# MM32F5277.net
KiCad netlist of a schematic drawn in Altium Designer
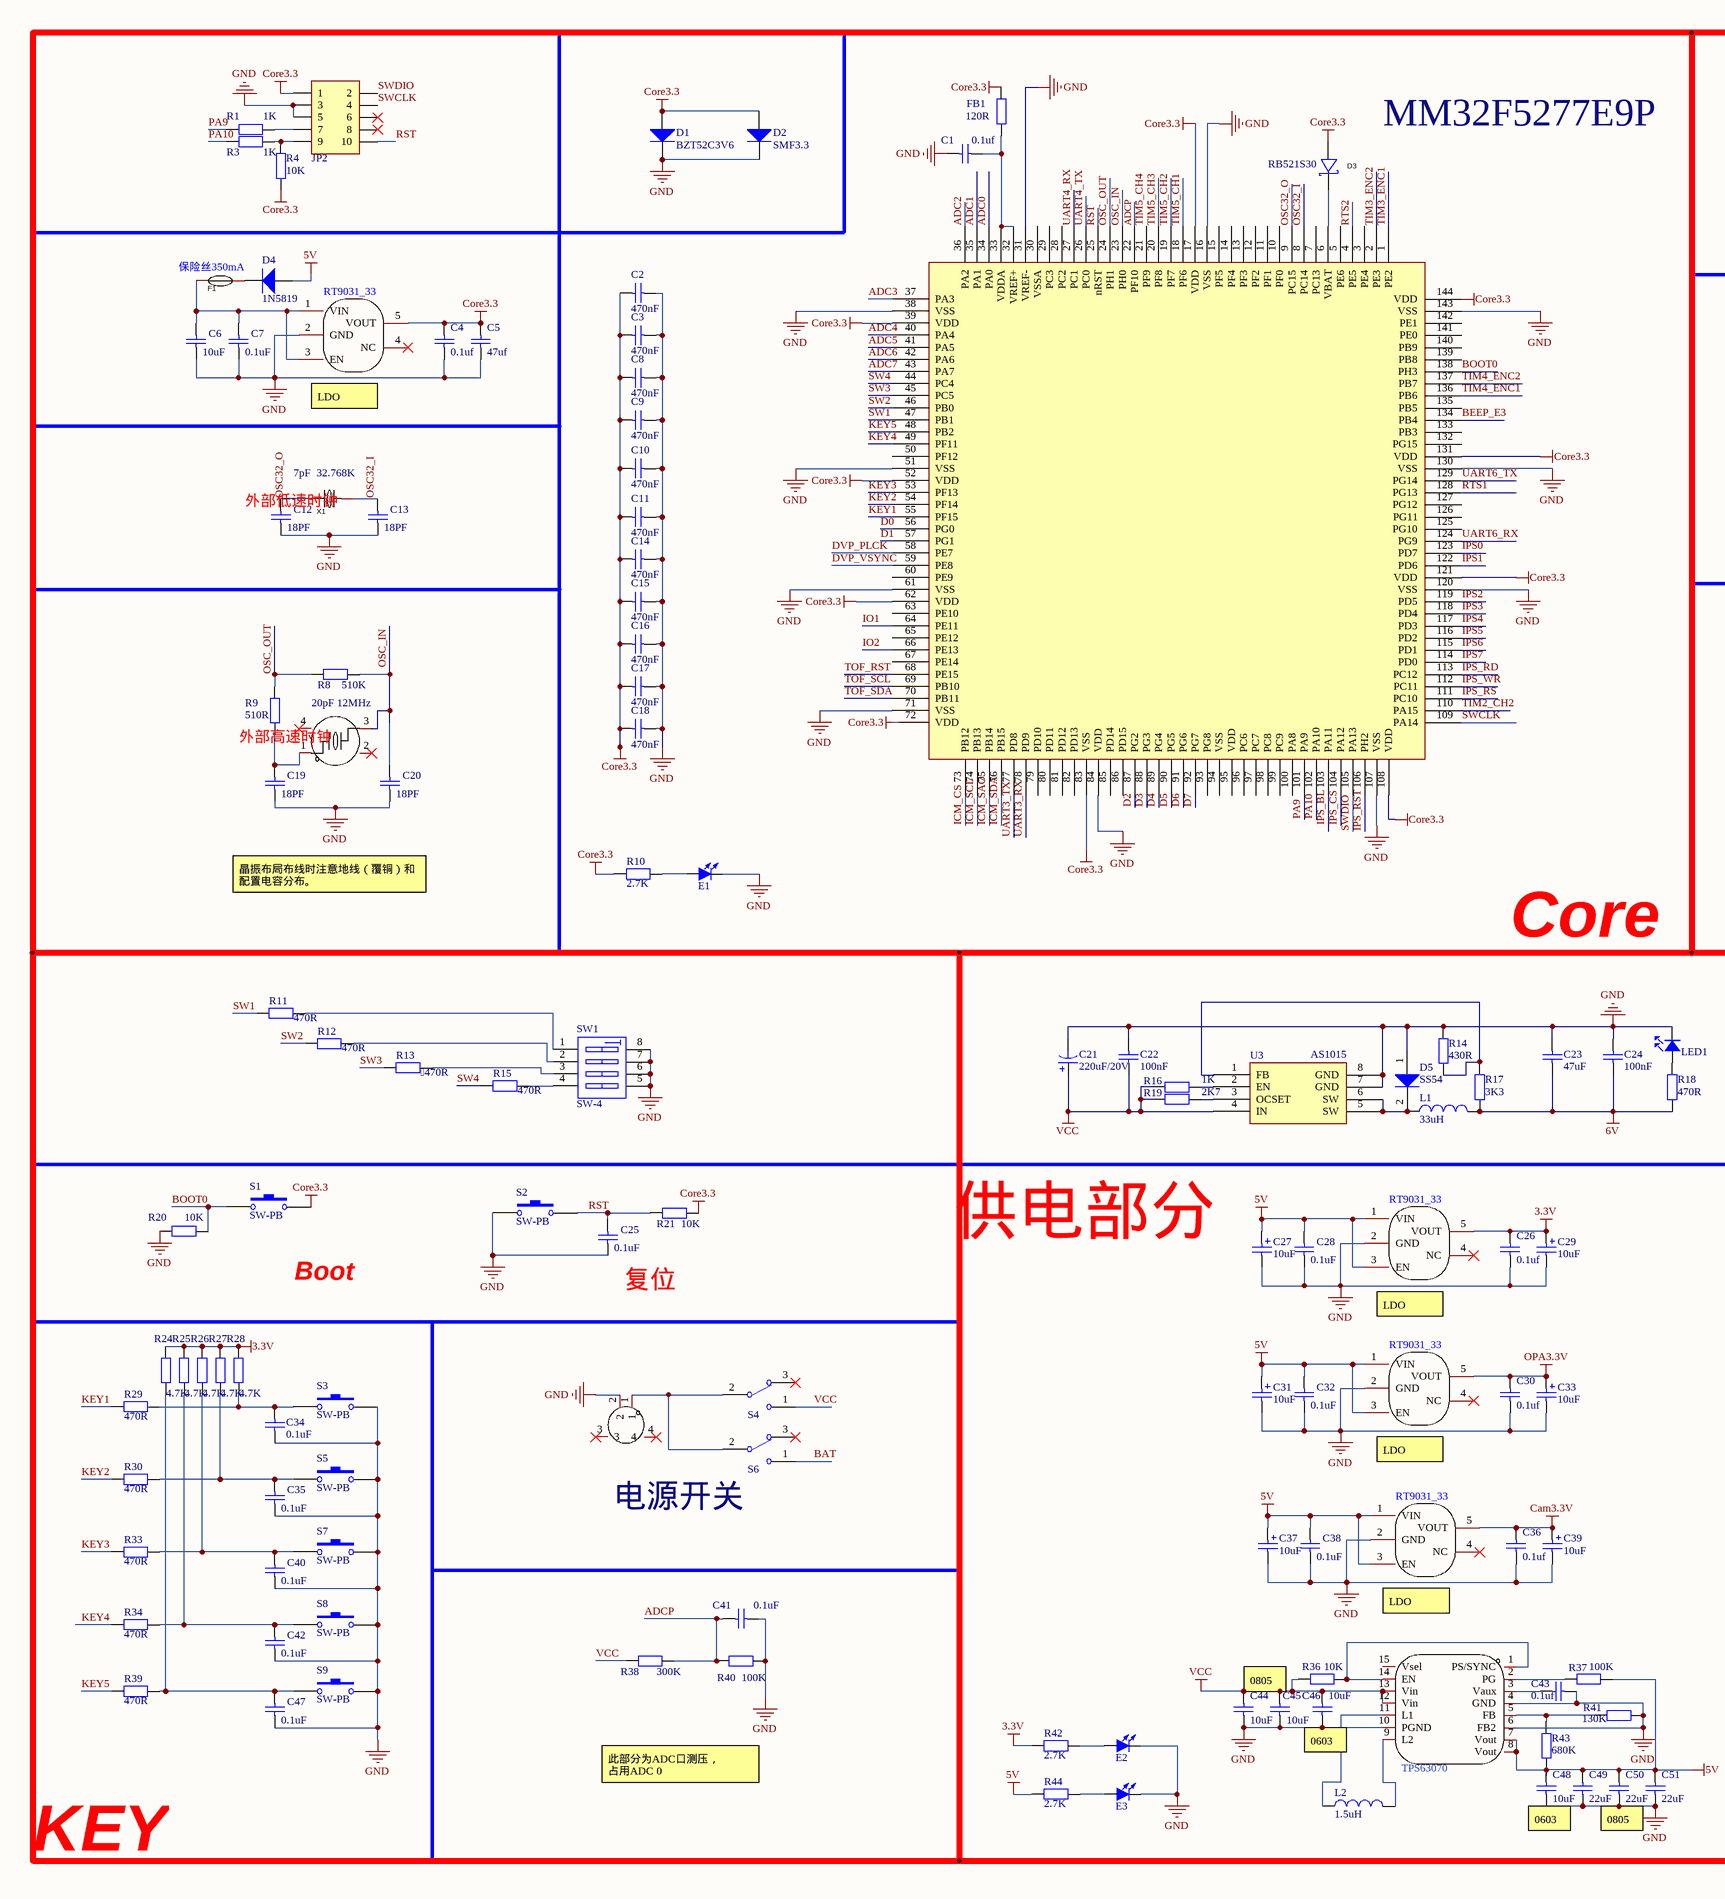
[diagram p0: MM32F5277.SchDoc, left]
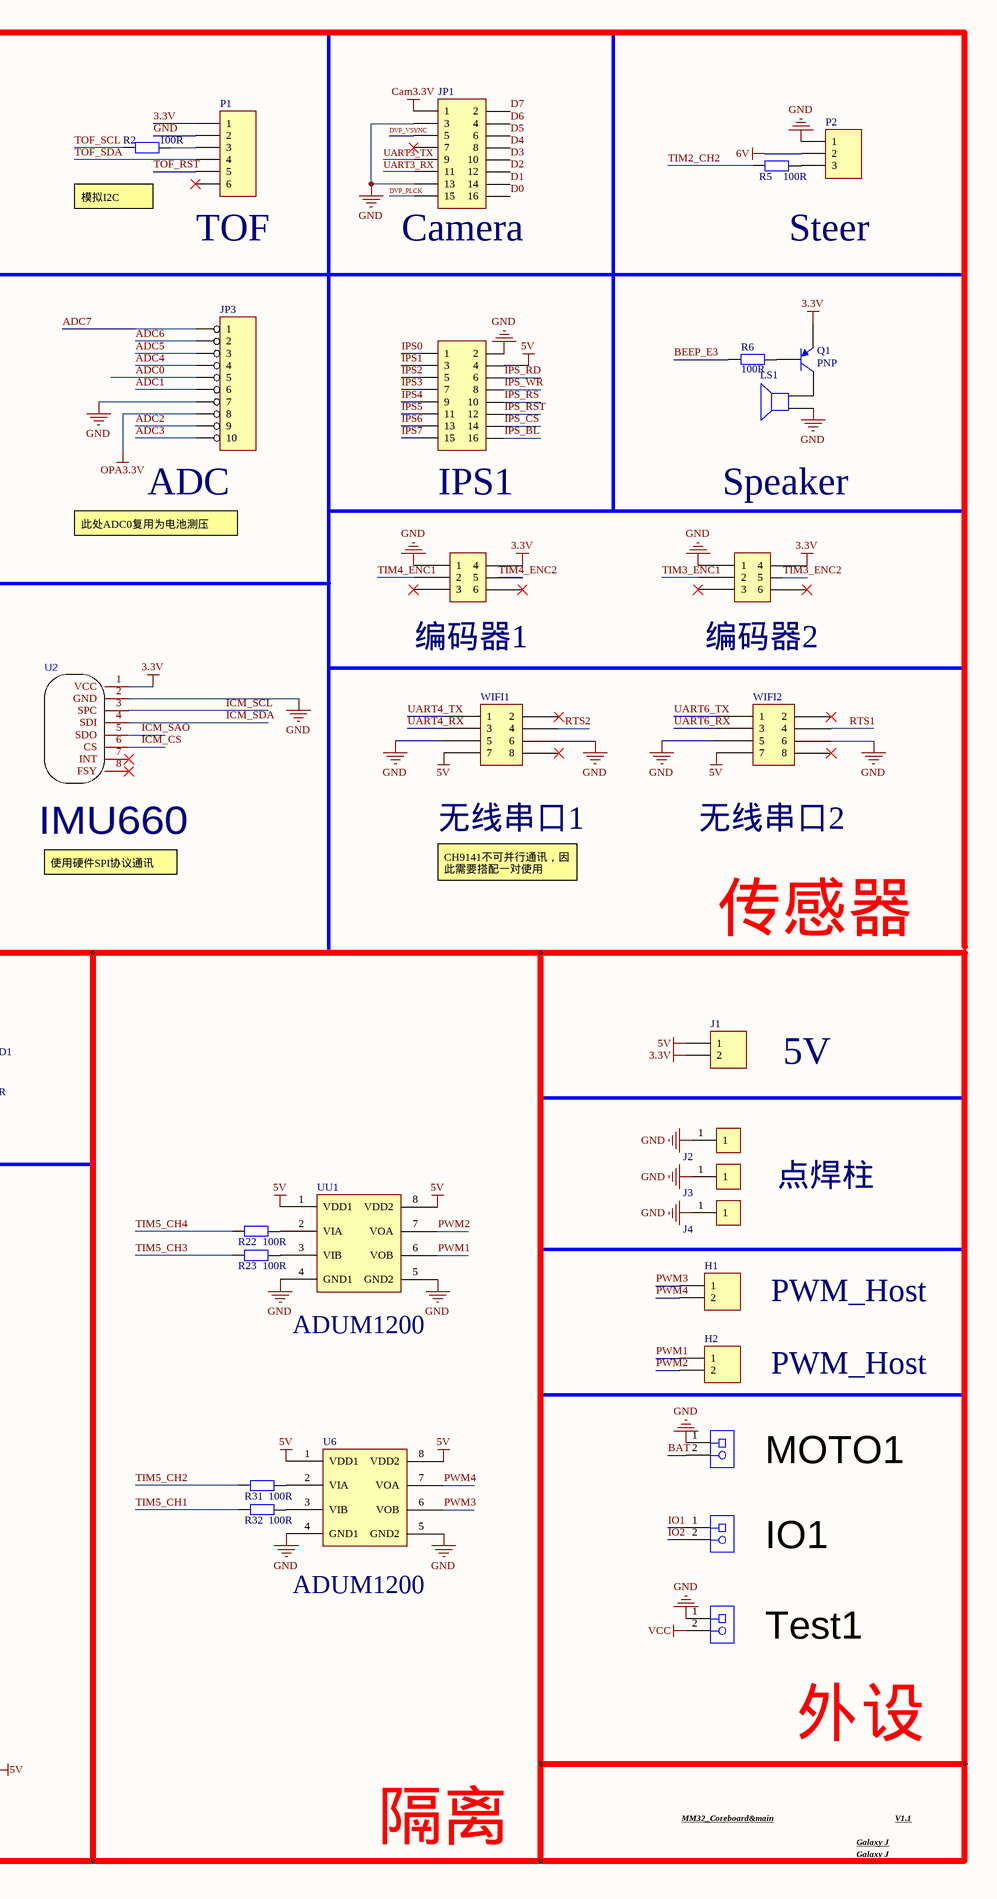
[diagram p1: MM32F5277.SchDoc, right]

(export (version "E")
  (design (tool "Eeschema 10.0.6"))
  (components
    (comp (ref "*1")
      (value "MM32F5277E9P")
      (footprint "LQFP-144_L20.0-W20.0-P0.50-LS22.0-BL")
      (libsource (lib "Mine") (part "MM32F3277G9P"))
    )
    (comp (ref "C1")
      (value "0.1uf")
      (footprint "C 0603_L")
      (fields (field (name "Comment") "Cap_4_1"))
      (libsource (lib "CAR-PCB") (part "Cap_4_1"))
    )
    (comp (ref "C2")
      (value "Cap_3")
      (footprint "C 0603_L")
      (description "Capacitor")
      (fields (field (name "ALTIUM_UNNAMED_1") "470nF"))
      (libsource (lib "CAR-PCB") (part "Cap_3"))
    )
    (comp (ref "C3")
      (value "Cap_3")
      (footprint "C 0603_L")
      (description "Capacitor")
      (fields (field (name "ALTIUM_UNNAMED_1") "470nF"))
      (libsource (lib "CAR-PCB") (part "Cap_3"))
    )
    (comp (ref "C4")
      (value "0.1uf")
      (footprint "C 0603_L")
      (fields (field (name "Comment") "Cap_4_1"))
      (libsource (lib "CAR-PCB") (part "Cap_4_1"))
    )
    (comp (ref "C5")
      (value "Cap_3")
      (footprint "C 0603_L")
      (description "Capacitor")
      (fields (field (name "ALTIUM_UNNAMED_1") "47uf"))
      (libsource (lib "CAR-PCB") (part "Cap_3"))
    )
    (comp (ref "C6")
      (value "10uF")
      (footprint "C 0603_L")
      (fields (field (name "Comment") "Cap_4_1"))
      (libsource (lib "CAR-PCB") (part "Cap_4_1"))
    )
    (comp (ref "C7")
      (value "Cap_3")
      (footprint "C 0603_L")
      (description "Capacitor")
      (fields (field (name "ALTIUM_UNNAMED_1") "0.1uF"))
      (libsource (lib "CAR-PCB") (part "Cap_3"))
    )
    (comp (ref "C8")
      (value "Cap_3")
      (footprint "C 0603_L")
      (description "Capacitor")
      (fields (field (name "ALTIUM_UNNAMED_1") "470nF"))
      (libsource (lib "CAR-PCB") (part "Cap_3"))
    )
    (comp (ref "C9")
      (value "Cap_3")
      (footprint "C 0603_L")
      (description "Capacitor")
      (fields (field (name "ALTIUM_UNNAMED_1") "470nF"))
      (libsource (lib "CAR-PCB") (part "Cap_3"))
    )
    (comp (ref "C10")
      (value "Cap_3")
      (footprint "C 0603_L")
      (description "Capacitor")
      (fields (field (name "ALTIUM_UNNAMED_1") "470nF"))
      (libsource (lib "CAR-PCB") (part "Cap_3"))
    )
    (comp (ref "C11")
      (value "Cap_3")
      (footprint "C 0603_L")
      (description "Capacitor")
      (fields (field (name "ALTIUM_UNNAMED_1") "470nF"))
      (libsource (lib "CAR-PCB") (part "Cap_3"))
    )
    (comp (ref "C12")
      (value "18PF")
      (footprint "C 0603_L")
      (fields (field (name "Comment") "Cap_4_1"))
      (libsource (lib "CAR-PCB") (part "Cap_4_1"))
    )
    (comp (ref "C13")
      (value "18PF")
      (footprint "C 0603_L")
      (fields (field (name "Comment") "Cap_4_1"))
      (libsource (lib "CAR-PCB") (part "Cap_4_1"))
    )
    (comp (ref "C14")
      (value "Cap_3")
      (footprint "C 0603_L")
      (description "Capacitor")
      (fields (field (name "ALTIUM_UNNAMED_1") "470nF"))
      (libsource (lib "CAR-PCB") (part "Cap_3"))
    )
    (comp (ref "C15")
      (value "Cap_3")
      (footprint "C 0603_L")
      (description "Capacitor")
      (fields (field (name "ALTIUM_UNNAMED_1") "470nF"))
      (libsource (lib "CAR-PCB") (part "Cap_3"))
    )
    (comp (ref "C16")
      (value "Cap_3")
      (footprint "C 0603_L")
      (description "Capacitor")
      (fields (field (name "ALTIUM_UNNAMED_1") "470nF"))
      (libsource (lib "CAR-PCB") (part "Cap_3"))
    )
    (comp (ref "C17")
      (value "Cap_3")
      (footprint "C 0603_L")
      (description "Capacitor")
      (fields (field (name "ALTIUM_UNNAMED_1") "470nF"))
      (libsource (lib "CAR-PCB") (part "Cap_3"))
    )
    (comp (ref "C18")
      (value "Cap_3")
      (footprint "C 0603_L")
      (description "Capacitor")
      (fields (field (name "ALTIUM_UNNAMED_1") "470nF"))
      (libsource (lib "CAR-PCB") (part "Cap_3"))
    )
    (comp (ref "C19")
      (value "18PF")
      (footprint "C 0603_L")
      (fields (field (name "Comment") "Cap_4_1"))
      (libsource (lib "CAR-PCB") (part "Cap_4_1"))
    )
    (comp (ref "C20")
      (value "18PF")
      (footprint "C 0603_L")
      (fields (field (name "Comment") "Cap_4_1"))
      (libsource (lib "CAR-PCB") (part "Cap_4_1"))
    )
    (comp (ref "C21")
      (value "220uF/20V")
      (footprint "CAP 5.0*10*12.5 - GD")
      (description "Polarized Capacitor (Radial)")
      (fields (field (name "PUBLISHER") "Altium Limited"))
      (libsource (lib "Miscellaneous Devices") (part "Cap Pol1"))
    )
    (comp (ref "C22")
      (value "100nF")
      (footprint "C 0603_L")
      (description "Capacitor")
      (fields (field (name "PUBLISHER") "Altium Limited"))
      (libsource (lib "Miscellaneous Devices") (part "Cap"))
    )
    (comp (ref "C23")
      (value "47uF")
      (footprint "C 1206_L")
      (description "Capacitor")
      (fields (field (name "PUBLISHER") "Altium Limited"))
      (libsource (lib "Miscellaneous Devices") (part "Cap"))
    )
    (comp (ref "C24")
      (value "100nF")
      (footprint "C 0603_L")
      (description "Capacitor")
      (fields (field (name "PUBLISHER") "Altium Limited"))
      (libsource (lib "Miscellaneous Devices") (part "Cap"))
    )
    (comp (ref "C25")
      (value "Cap_3")
      (footprint "C 0603_L")
      (description "Capacitor")
      (fields (field (name "ALTIUM_UNNAMED_1") "0.1uF"))
      (libsource (lib "CAR-PCB") (part "Cap_3"))
    )
    (comp (ref "C26")
      (value "0.1uf")
      (footprint "C 0603_L")
      (fields (field (name "Comment") "Cap_4_1"))
      (libsource (lib "CAR-PCB") (part "Cap_4_1"))
    )
    (comp (ref "C27")
      (value "10uF")
      (footprint "C3216A - duplicate - duplicate")
      (description "Polarized Capacitor (Radial)")
      (fields (field (name "Comment") "Cap Pol1") (field (name "PUBLISHER") "Altium Limited"))
      (libsource (lib "CAR-PCB") (part "Cap Pol1_1"))
    )
    (comp (ref "C28")
      (value "Cap_3")
      (footprint "C 0603_L")
      (description "Capacitor")
      (fields (field (name "ALTIUM_UNNAMED_1") "0.1uF"))
      (libsource (lib "CAR-PCB") (part "Cap_3"))
    )
    (comp (ref "C29")
      (value "10uF")
      (footprint "C3216A - duplicate - duplicate")
      (description "Polarized Capacitor (Radial)")
      (fields (field (name "Comment") "Cap Pol1") (field (name "PUBLISHER") "Altium Limited"))
      (libsource (lib "CAR-PCB") (part "Cap Pol1_1"))
    )
    (comp (ref "C30")
      (value "0.1uf")
      (footprint "C 0603_L")
      (fields (field (name "Comment") "Cap_4_1"))
      (libsource (lib "CAR-PCB") (part "Cap_4_1"))
    )
    (comp (ref "C31")
      (value "10uF")
      (footprint "C3216A - duplicate - duplicate")
      (description "Polarized Capacitor (Radial)")
      (fields (field (name "Comment") "Cap Pol1") (field (name "PUBLISHER") "Altium Limited"))
      (libsource (lib "CAR-PCB") (part "Cap Pol1_1"))
    )
    (comp (ref "C32")
      (value "Cap_3")
      (footprint "C 0603_L")
      (description "Capacitor")
      (fields (field (name "ALTIUM_UNNAMED_1") "0.1uF"))
      (libsource (lib "CAR-PCB") (part "Cap_3"))
    )
    (comp (ref "C33")
      (value "10uF")
      (footprint "C3216A - duplicate - duplicate")
      (description "Polarized Capacitor (Radial)")
      (fields (field (name "Comment") "Cap Pol1") (field (name "PUBLISHER") "Altium Limited"))
      (libsource (lib "CAR-PCB") (part "Cap Pol1_1"))
    )
    (comp (ref "C34")
      (value "Cap_3")
      (footprint "C 0603_L")
      (description "Capacitor")
      (fields (field (name "ALTIUM_UNNAMED_1") "0.1uF"))
      (libsource (lib "CAR-PCB") (part "Cap_3"))
    )
    (comp (ref "C35")
      (value "Cap_3")
      (footprint "C 0603_L")
      (description "Capacitor")
      (fields (field (name "ALTIUM_UNNAMED_1") "0.1uF"))
      (libsource (lib "CAR-PCB") (part "Cap_3"))
    )
    (comp (ref "C36")
      (value "0.1uf")
      (footprint "C 0603_L")
      (fields (field (name "Comment") "Cap_4_1"))
      (libsource (lib "CAR-PCB") (part "Cap_4_1"))
    )
    (comp (ref "C37")
      (value "10uF")
      (footprint "C3216A - duplicate - duplicate")
      (description "Polarized Capacitor (Radial)")
      (fields (field (name "Comment") "Cap Pol1") (field (name "PUBLISHER") "Altium Limited"))
      (libsource (lib "CAR-PCB") (part "Cap Pol1_1"))
    )
    (comp (ref "C38")
      (value "Cap_3")
      (footprint "C 0603_L")
      (description "Capacitor")
      (fields (field (name "ALTIUM_UNNAMED_1") "0.1uF"))
      (libsource (lib "CAR-PCB") (part "Cap_3"))
    )
    (comp (ref "C39")
      (value "10uF")
      (footprint "C3216A - duplicate - duplicate")
      (description "Polarized Capacitor (Radial)")
      (fields (field (name "Comment") "Cap Pol1") (field (name "PUBLISHER") "Altium Limited"))
      (libsource (lib "CAR-PCB") (part "Cap Pol1_1"))
    )
    (comp (ref "C40")
      (value "Cap_3")
      (footprint "C 0603_L")
      (description "Capacitor")
      (fields (field (name "ALTIUM_UNNAMED_1") "0.1uF"))
      (libsource (lib "CAR-PCB") (part "Cap_3"))
    )
    (comp (ref "C41")
      (value "Cap_3")
      (footprint "C 0603_L")
      (description "Capacitor")
      (fields (field (name "ALTIUM_UNNAMED_1") "0.1uF"))
      (libsource (lib "CAR-PCB") (part "Cap_3"))
    )
    (comp (ref "C42")
      (value "Cap_3")
      (footprint "C 0603_L")
      (description "Capacitor")
      (fields (field (name "ALTIUM_UNNAMED_1") "0.1uF"))
      (libsource (lib "CAR-PCB") (part "Cap_3"))
    )
    (comp (ref "C43")
      (value "0.1uf")
      (footprint "C 0603_L")
      (fields (field (name "Comment") "Cap_4_1"))
      (libsource (lib "CAR-PCB") (part "Cap_4_1"))
    )
    (comp (ref "C44")
      (value "10uF")
      (footprint "C 0805_L")
      (fields (field (name "Comment") "Cap_4_1"))
      (libsource (lib "CAR-PCB") (part "Cap_4_1"))
    )
    (comp (ref "C45")
      (value "10uF")
      (footprint "C 0805_L")
      (fields (field (name "Comment") "Cap_4_1"))
      (libsource (lib "CAR-PCB") (part "Cap_4_1"))
    )
    (comp (ref "C46")
      (value "10uF")
      (footprint "C 0603_L")
      (fields (field (name "Comment") "Cap_4_1"))
      (libsource (lib "CAR-PCB") (part "Cap_4_1"))
    )
    (comp (ref "C47")
      (value "Cap_3")
      (footprint "C 0603_L")
      (description "Capacitor")
      (fields (field (name "ALTIUM_UNNAMED_1") "0.1uF"))
      (libsource (lib "CAR-PCB") (part "Cap_3"))
    )
    (comp (ref "C48")
      (value "10uF")
      (footprint "C 0603_L")
      (fields (field (name "Comment") "Cap_4_1"))
      (libsource (lib "CAR-PCB") (part "Cap_4_1"))
    )
    (comp (ref "C49")
      (value "22uF")
      (footprint "C 0805_L")
      (fields (field (name "Comment") "Cap_4_1"))
      (libsource (lib "CAR-PCB") (part "Cap_4_1"))
    )
    (comp (ref "C50")
      (value "22uF")
      (footprint "C 0805_L")
      (fields (field (name "Comment") "Cap_4_1"))
      (libsource (lib "CAR-PCB") (part "Cap_4_1"))
    )
    (comp (ref "C51")
      (value "22uF")
      (footprint "C 0805_L")
      (fields (field (name "Comment") "Cap_4_1"))
      (libsource (lib "CAR-PCB") (part "Cap_4_1"))
    )
    (comp (ref "CN1")
      (value "XT30PW-M")
      (footprint "XT30PW-M")
      (fields (field (name "MANUFACTURER") "AMASS(艾迈斯)"))
      (libsource (lib "XT30PW-M1_XT30PW-M") (part "XT30PW-M"))
    )
    (comp (ref "D1")
      (value "BZT52C3V6")
      (footprint "SOD-123")
      (description "SMT Glass Diode, PSpice Model")
      (fields (field (name "PARTNUMBER") "BZT52C3V6") (field (name "PUBLISHER") "Altium Limited"))
      (libsource (lib "altium-import") (part "root_3_Diode 1N4148_"))
    )
    (comp (ref "D2")
      (value "SMF3.3")
      (footprint "SOD-123")
      (description "SMT Glass Diode, PSpice Model")
      (fields (field (name "PARTNUMBER") "SMF3.3") (field (name "PUBLISHER") "Altium Limited"))
      (libsource (lib "altium-import") (part "root_3_Diode 1N4148_"))
    )
    (comp (ref "D3")
      (value "RB521S30")
      (footprint "SOD-523_L1.2-W0.8-LS1.6-RD")
      (fields (field (name "MANUFACTURER") "onsemi(安森美)"))
      (libsource (lib "Schlib1") (part "RB521S30"))
    )
    (comp (ref "D4")
      (value "1N5819")
      (footprint "SOD-123")
      (description "SMT Glass Diode, PSpice Model")
      (fields (field (name "PARTNUMBER") "1N5819") (field (name "PUBLISHER") "Altium Limited"))
      (libsource (lib "altium-import") (part "root_2_Diode 1N4148_"))
    )
    (comp (ref "D5")
      (value "SS54")
      (footprint "SMA")
      (description "3 Amp Medium Power Silicon Rectifier Diode")
      (fields (field (name "PUBLISHER") "Altium Limited"))
      (libsource (lib "Miscellaneous Devices") (part "Diode 1N5408"))
    )
    (comp (ref "E1")
      (value "红色")
      (footprint "LED 0603")
      (description "贴片LED")
      (fields (field (name "版权归属") "黎明电子style"))
      (libsource (lib "CAR-PCB") (part "LED-SMD"))
    )
    (comp (ref "E2")
      (value "红色")
      (footprint "LED 0603")
      (description "贴片LED")
      (fields (field (name "版权归属") "黎明电子style"))
      (libsource (lib "CAR-PCB") (part "LED-SMD"))
    )
    (comp (ref "E3")
      (value "红色")
      (footprint "LED 0603")
      (description "贴片LED")
      (fields (field (name "版权归属") "黎明电子style"))
      (libsource (lib "CAR-PCB") (part "LED-SMD"))
    )
    (comp (ref "F1")
      (value "0603L050SLYR")
      (footprint "FU 0805")
      (fields (field (name "MANUFACTURER") "Littelfuse(美国力特)"))
      (libsource (lib "6V500mA") (part "0603L050SLYR"))
    )
    (comp (ref "FB1")
      (value "120R")
      (footprint "R 0603_L")
      (description "FB")
      (fields (field (name "PUBLISHER") "Altium Limited"))
      (libsource (lib "") (part "Res2_1"))
    )
    (comp (ref "H1")
      (value "PWM_Host")
      (footprint "HX2.54-2")
      (description "Header, 2-Pin")
      (fields (field (name "PUBLISHER") "Altium Limited"))
      (libsource (lib "Miscellaneous Connectors") (part "Header 2"))
    )
    (comp (ref "H2")
      (value "PWM_Host")
      (footprint "HX2.54-2")
      (description "Header, 2-Pin")
      (fields (field (name "PUBLISHER") "Altium Limited"))
      (libsource (lib "Miscellaneous Connectors") (part "Header 2"))
    )
    (comp (ref "IO1")
      (value "KF301-2P")
      (footprint "HDR1X2")
      (description "IO")
      (fields
        (field (name "PARTNUMBER") "691 101 710 002")
        (field (name "MANUFACTURER") "Wurth Elektronik eiSos")
        (field (name "SYMBOLCREATOR") "a0412235")
        (field (name "PUBLISHER") "Texas Instruments")
      )
      (libsource (lib "LQ-PCB(1)") (part "691 101 710 001"))
    )
    (comp (ref "IPS1")
      (value "Header 8X2")
      (footprint "HDR-8X2")
      (description "8*2P接插件")
      (fields (field (name "版权归属") "黎明电子style"))
      (libsource (lib "LQTC(逐飞)") (part "Header 8X2"))
    )
    (comp (ref "J1")
      (value "5V")
      (footprint "HDR2.54-1X2")
      (description "Header, 2-Pin")
      (fields (field (name "PUBLISHER") "Altium Limited"))
      (libsource (lib "Miscellaneous Connectors") (part "Header 2"))
    )
    (comp (ref "J2") (value "Column") (footprint "Column") (libsource (lib "Schlib1") (part "Component_1")))
    (comp (ref "J3") (value "Column") (footprint "Column") (libsource (lib "Schlib1") (part "Component_1")))
    (comp (ref "J4") (value "点焊柱") (footprint "Column") (libsource (lib "Schlib1") (part "Component_1")))
    (comp (ref "JP1") (value "Camera") (footprint "Cam_HDR2X8") (libsource (lib "CAR-PCB") (part "Camera")))
    (comp (ref "JP2")
      (value "Header 5X2")
      (footprint "HDR2.54-LI-2x5P")
      (description "5*2P接插件")
      (libsource (lib "18 - 接插件-脚距2.54mm (100mil) ") (part "Header 5X2"))
    )
    (comp (ref "JP3")
      (value "ADC")
      (footprint "HDR1X10")
      (libsource (lib "Miscellaneous Devices") (part "HEADER 10"))
    )
    (comp (ref "L1")
      (value "33uH")
      (footprint "L-SMD-0630")
      (description "Inductor")
      (fields (field (name "PUBLISHER") "Altium Limited"))
      (libsource (lib "Miscellaneous Devices") (part "Inductor"))
    )
    (comp (ref "L2")
      (value "1.5uH")
      (footprint "L-SMD-0630")
      (description "Inductor")
      (fields (field (name "PUBLISHER") "Altium Limited"))
      (libsource (lib "Miscellaneous Devices") (part "Inductor"))
    )
    (comp (ref "LED1") (value "LED-SM") (footprint "LED 0603") (libsource (lib "LZLIB2010") (part "LED-SM")))
    (comp (ref "LS1")
      (value "Speaker")
      (footprint "BEEP 9x5.5mm")
      (description "Loudspeaker")
      (fields (field (name "PUBLISHER") "Altium Limited"))
      (libsource (lib "2014主板3.0") (part "Speaker"))
    )
    (comp (ref "mini*1")
      (value "编码器2")
      (footprint "DC-2.54-L-Z-6P")
      (libsource (lib "LQ-PCB(1)") (part "Component_1"))
    )
    (comp (ref "mini1")
      (value "编码器1")
      (footprint "DC-2.54-L-Z-6P")
      (libsource (lib "LQ-PCB(1)") (part "Component_1"))
    )
    (comp (ref "MOTO1")
      (value "KF301-2P")
      (footprint "XT30UPB-F")
      (fields
        (field (name "PARTNUMBER") "691 101 710 002")
        (field (name "MANUFACTURER") "Wurth Elektronik eiSos")
        (field (name "SYMBOLCREATOR") "a0412235")
        (field (name "PUBLISHER") "Texas Instruments")
      )
      (libsource (lib "LQ-PCB(1)") (part "691 101 710 001"))
    )
    (comp (ref "P1")
      (value "TOF")
      (footprint "HDR1X6-M")
      (description "Header, 6-Pin")
      (fields (field (name "PUBLISHER") "Altium Limited"))
      (libsource (lib "Miscellaneous Connectors") (part "Header 6"))
    )
    (comp (ref "P2")
      (value "Steer")
      (footprint "HDR2.54-LI-3P")
      (description "Header, 3-Pin")
      (fields (field (name "PUBLISHER") "Altium Limited"))
      (libsource (lib "LQ-PCB(1)") (part "Header 3"))
    )
    (comp (ref "Q1")
      (value "PNP")
      (footprint "SOT23-3L")
      (description "PNP Bipolar Transistor")
      (fields (field (name "PUBLISHER") "Altium Limited"))
      (libsource (lib "20170112") (part "PNP"))
    )
    (comp (ref "R1")
      (value "1K")
      (footprint "R 0603_L")
      (description "Resistor")
      (fields (field (name "Comment") "Res2") (field (name "PUBLISHER") "Altium Limited"))
      (libsource (lib "LQ-PCB(1)") (part "Res2"))
    )
    (comp (ref "R2")
      (value "100R")
      (footprint "R 0603_L")
      (description "Resistor")
      (fields (field (name "Comment") "Res2") (field (name "PUBLISHER") "Altium Limited"))
      (libsource (lib "LQ-PCB(1)") (part "Res2"))
    )
    (comp (ref "R3")
      (value "1K")
      (footprint "R 0603_L")
      (description "Resistor")
      (fields (field (name "Comment") "Res2") (field (name "PUBLISHER") "Altium Limited"))
      (libsource (lib "LQ-PCB(1)") (part "Res2"))
    )
    (comp (ref "R4")
      (value "10K")
      (footprint "R 0603_L")
      (description "Resistor")
      (fields (field (name "Comment") "Res2") (field (name "PUBLISHER") "Altium Limited"))
      (libsource (lib "") (part "Res2_1"))
    )
    (comp (ref "R5")
      (value "100R")
      (footprint "R 0603_L")
      (description "Resistor")
      (fields (field (name "Comment") "Res2") (field (name "PUBLISHER") "Altium Limited"))
      (libsource (lib "LQ-PCB(1)") (part "Res2"))
    )
    (comp (ref "R6")
      (value "100R")
      (footprint "R 0603_L")
      (fields (field (name "Comment") "Res2_3"))
      (libsource (lib "") (part "Res2_3_1"))
    )
    (comp (ref "R8")
      (value "510K")
      (footprint "R 0603_L")
      (description "Resistor")
      (fields (field (name "Comment") "Res2") (field (name "PUBLISHER") "Altium Limited"))
      (libsource (lib "LQ-PCB(1)") (part "Res2"))
    )
    (comp (ref "R9")
      (value "510R")
      (footprint "R 0603_L")
      (description "Resistor")
      (fields (field (name "Comment") "Res2") (field (name "PUBLISHER") "Altium Limited"))
      (libsource (lib "") (part "Res2_1"))
    )
    (comp (ref "R10")
      (value "2.7K")
      (footprint "R 0603_L")
      (fields (field (name "Comment") "Res2_3"))
      (libsource (lib "") (part "Res2_3_1"))
    )
    (comp (ref "R11")
      (value "470R")
      (footprint "R 0603_L")
      (description "Resistor")
      (fields (field (name "Comment") "Res2") (field (name "PUBLISHER") "Altium Limited"))
      (libsource (lib "") (part "Res2_2_1"))
    )
    (comp (ref "R12")
      (value "470R")
      (footprint "R 0603_L")
      (description "Resistor")
      (fields (field (name "Comment") "Res2") (field (name "PUBLISHER") "Altium Limited"))
      (libsource (lib "") (part "Res2_2_1"))
    )
    (comp (ref "R13")
      (value "470R")
      (footprint "R 0603_L")
      (description "Resistor")
      (fields (field (name "Comment") "Res2") (field (name "PUBLISHER") "Altium Limited"))
      (libsource (lib "") (part "Res2_2_1"))
    )
    (comp (ref "R14")
      (value "430R")
      (footprint "R 0603_L")
      (description "Resistor")
      (fields (field (name "PUBLISHER") "Altium Limited"))
      (libsource (lib "") (part "R6_1"))
    )
    (comp (ref "R15")
      (value "470R")
      (footprint "R 0603_L")
      (description "Resistor")
      (fields (field (name "Comment") "Res2") (field (name "PUBLISHER") "Altium Limited"))
      (libsource (lib "") (part "Res2_2_1"))
    )
    (comp (ref "R16")
      (value "1K")
      (footprint "R 0603_L")
      (description "Resistor")
      (fields (field (name "PUBLISHER") "Altium Limited"))
      (libsource (lib "YUNFANG") (part "R6"))
    )
    (comp (ref "R17")
      (value "3K3")
      (footprint "R 0603_L")
      (description "Resistor")
      (fields (field (name "PUBLISHER") "Altium Limited"))
      (libsource (lib "") (part "R6_1"))
    )
    (comp (ref "R18")
      (value "470R")
      (footprint "R 0603_L")
      (description "Resistor")
      (fields (field (name "PUBLISHER") "Altium Limited"))
      (libsource (lib "") (part "R6_2"))
    )
    (comp (ref "R19")
      (value "2K7")
      (footprint "R 0603_L")
      (description "Resistor")
      (fields (field (name "PUBLISHER") "Altium Limited"))
      (libsource (lib "YUNFANG") (part "R6"))
    )
    (comp (ref "R20")
      (value "10K")
      (footprint "R 0603_L")
      (description "Resistor")
      (fields (field (name "Comment") "Res2") (field (name "PUBLISHER") "Altium Limited"))
      (libsource (lib "LQ-PCB(1)") (part "Res2"))
    )
    (comp (ref "R21")
      (value "10K")
      (footprint "R 0603_L")
      (description "Resistor")
      (fields (field (name "Comment") "Res2") (field (name "PUBLISHER") "Altium Limited"))
      (libsource (lib "LQ-PCB(1)") (part "Res2"))
    )
    (comp (ref "R22")
      (value "100R")
      (footprint "R 0603_L")
      (description "Resistor")
      (fields (field (name "Comment") "Res2") (field (name "PUBLISHER") "Altium Limited"))
      (libsource (lib "LQ-PCB(1)") (part "Res2"))
    )
    (comp (ref "R23")
      (value "100R")
      (footprint "R 0603_L")
      (description "Resistor")
      (fields (field (name "Comment") "Res2") (field (name "PUBLISHER") "Altium Limited"))
      (libsource (lib "LQ-PCB(1)") (part "Res2"))
    )
    (comp (ref "R24")
      (value "4.7K")
      (footprint "R 0603_L")
      (description "Resistor")
      (fields (field (name "Comment") "Res2") (field (name "PUBLISHER") "Altium Limited"))
      (libsource (lib "CAR-PCB") (part "Res2_2"))
    )
    (comp (ref "R25")
      (value "4.7K")
      (footprint "R 0603_L")
      (description "Resistor")
      (fields (field (name "Comment") "Res2") (field (name "PUBLISHER") "Altium Limited"))
      (libsource (lib "CAR-PCB") (part "Res2_2"))
    )
    (comp (ref "R26")
      (value "4.7K")
      (footprint "R 0603_L")
      (description "Resistor")
      (fields (field (name "Comment") "Res2") (field (name "PUBLISHER") "Altium Limited"))
      (libsource (lib "CAR-PCB") (part "Res2_2"))
    )
    (comp (ref "R27")
      (value "4.7K")
      (footprint "R 0603_L")
      (description "Resistor")
      (fields (field (name "Comment") "Res2") (field (name "PUBLISHER") "Altium Limited"))
      (libsource (lib "CAR-PCB") (part "Res2_2"))
    )
    (comp (ref "R28")
      (value "4.7K")
      (footprint "R 0603_L")
      (description "Resistor")
      (fields (field (name "Comment") "Res2") (field (name "PUBLISHER") "Altium Limited"))
      (libsource (lib "CAR-PCB") (part "Res2_2"))
    )
    (comp (ref "R29")
      (value "470R")
      (footprint "R 0603_L")
      (description "Resistor")
      (fields (field (name "Comment") "Res2") (field (name "PUBLISHER") "Altium Limited"))
      (libsource (lib "") (part "Res2_2_1"))
    )
    (comp (ref "R30")
      (value "470R")
      (footprint "R 0603_L")
      (description "Resistor")
      (fields (field (name "Comment") "Res2") (field (name "PUBLISHER") "Altium Limited"))
      (libsource (lib "") (part "Res2_2_1"))
    )
    (comp (ref "R31")
      (value "100R")
      (footprint "R 0603_L")
      (description "Resistor")
      (fields (field (name "Comment") "Res2") (field (name "PUBLISHER") "Altium Limited"))
      (libsource (lib "LQ-PCB(1)") (part "Res2"))
    )
    (comp (ref "R32")
      (value "100R")
      (footprint "R 0603_L")
      (description "Resistor")
      (fields (field (name "Comment") "Res2") (field (name "PUBLISHER") "Altium Limited"))
      (libsource (lib "LQ-PCB(1)") (part "Res2"))
    )
    (comp (ref "R33")
      (value "470R")
      (footprint "R 0603_L")
      (description "Resistor")
      (fields (field (name "Comment") "Res2") (field (name "PUBLISHER") "Altium Limited"))
      (libsource (lib "") (part "Res2_2_1"))
    )
    (comp (ref "R34")
      (value "470R")
      (footprint "R 0603_L")
      (description "Resistor")
      (fields (field (name "Comment") "Res2") (field (name "PUBLISHER") "Altium Limited"))
      (libsource (lib "") (part "Res2_2_1"))
    )
    (comp (ref "R36")
      (value "10K")
      (footprint "R 0603_L")
      (fields (field (name "Comment") "Res2_3"))
      (libsource (lib "") (part "Res2_3_2"))
    )
    (comp (ref "R37")
      (value "100K")
      (footprint "R 0603_L")
      (fields (field (name "Comment") "Res2_3"))
      (libsource (lib "") (part "Res2_3_2"))
    )
    (comp (ref "R38")
      (value "300K")
      (footprint "R 0603_L")
      (description "Resistor")
      (fields (field (name "Comment") "Res2") (field (name "PUBLISHER") "Altium Limited"))
      (libsource (lib "LQ-PCB(1)") (part "Res2"))
    )
    (comp (ref "R39")
      (value "470R")
      (footprint "R 0603_L")
      (description "Resistor")
      (fields (field (name "Comment") "Res2") (field (name "PUBLISHER") "Altium Limited"))
      (libsource (lib "") (part "Res2_2_1"))
    )
    (comp (ref "R40")
      (value "100K")
      (footprint "R 0603_L")
      (description "Resistor")
      (fields (field (name "Comment") "Res2") (field (name "PUBLISHER") "Altium Limited"))
      (libsource (lib "LQ-PCB(1)") (part "Res2"))
    )
    (comp (ref "R41")
      (value "130K")
      (footprint "R 0603_L")
      (fields (field (name "Comment") "Res2_3"))
      (libsource (lib "") (part "Res2_3_1"))
    )
    (comp (ref "R42")
      (value "2.7K")
      (footprint "R 0603_L")
      (fields (field (name "Comment") "Res2_3"))
      (libsource (lib "") (part "Res2_3_1"))
    )
    (comp (ref "R43")
      (value "680K")
      (footprint "R 0603_L")
      (fields (field (name "Comment") "Res2_3"))
      (libsource (lib "CAR-PCB") (part "Res2_3"))
    )
    (comp (ref "R44")
      (value "2.7K")
      (footprint "R 0603_L")
      (fields (field (name "Comment") "Res2_3"))
      (libsource (lib "") (part "Res2_3_1"))
    )
    (comp (ref "S1")
      (value "SW-PB")
      (footprint "PTS810-3*4-CurvePin")
      (description "微动开关")
      (fields (field (name "PUBLISHER") "Altium Limited"))
      (libsource (lib "0.7 - 常用按键-开关") (part "SW-PB"))
    )
    (comp (ref "S2")
      (value "SW-PB")
      (footprint "PTS810-3*4-CurvePin")
      (description "微动开关")
      (fields (field (name "PUBLISHER") "Altium Limited"))
      (libsource (lib "0.7 - 常用按键-开关") (part "SW-PB"))
    )
    (comp (ref "S3")
      (value "SW-PB")
      (footprint "PTS810-3*4-CurvePin")
      (description "微动开关")
      (fields (field (name "PUBLISHER") "Altium Limited"))
      (libsource (lib "0.7 - 常用按键-开关") (part "SW-PB"))
    )
    (comp (ref "S4")
      (value "SW-SPDT")
      (footprint "SS12D10")
      (description "单刀双掷开关 3脚船型、钮子、拨动开关 SPDT Subminiature Toggle Switch")
      (fields (field (name "PUBLISHER") "Altium Limited"))
      (libsource (lib "钮子开关原理") (part "SW-SPDT"))
    )
    (comp (ref "S5")
      (value "SW-PB")
      (footprint "PTS810-3*4-CurvePin")
      (description "微动开关")
      (fields (field (name "PUBLISHER") "Altium Limited"))
      (libsource (lib "0.7 - 常用按键-开关") (part "SW-PB"))
    )
    (comp (ref "S6")
      (value "SW-SPDT")
      (footprint "SS12D10")
      (description "单刀双掷开关 3脚船型、钮子、拨动开关 SPDT Subminiature Toggle Switch")
      (fields (field (name "PUBLISHER") "Altium Limited"))
      (libsource (lib "钮子开关原理") (part "SW-SPDT"))
    )
    (comp (ref "S7")
      (value "SW-PB")
      (footprint "PTS810-3*4-CurvePin")
      (description "微动开关")
      (fields (field (name "PUBLISHER") "Altium Limited"))
      (libsource (lib "0.7 - 常用按键-开关") (part "SW-PB"))
    )
    (comp (ref "S8")
      (value "SW-PB")
      (footprint "PTS810-3*4-CurvePin")
      (description "微动开关")
      (fields (field (name "PUBLISHER") "Altium Limited"))
      (libsource (lib "0.7 - 常用按键-开关") (part "SW-PB"))
    )
    (comp (ref "S9")
      (value "SW-PB")
      (footprint "PTS810-3*4-CurvePin")
      (description "微动开关")
      (fields (field (name "PUBLISHER") "Altium Limited"))
      (libsource (lib "0.7 - 常用按键-开关") (part "SW-PB"))
    )
    (comp (ref "SW1") (value "SW-4") (footprint "SOP-KEY4") (libsource (lib "LQ-PCB(1)") (part "SW-4")))
    (comp (ref "Test1")
      (value "KF301-2P")
      (footprint "HDR2.54-1X2 - duplicate1")
      (fields
        (field (name "PARTNUMBER") "691 101 710 002")
        (field (name "MANUFACTURER") "Wurth Elektronik eiSos")
        (field (name "SYMBOLCREATOR") "a0412235")
        (field (name "PUBLISHER") "Texas Instruments")
      )
      (libsource (lib "LQ-PCB(1)") (part "691 101 710 001"))
    )
    (comp (ref "U1")
      (value "RT9013-33GB")
      (footprint "MM32F5277主板封装库:SOT-23-5")
      (fields (field (name "MANUFACTURER") "RICHTEK(台湾立锜)"))
      (libsource (lib "RT9013-33GB") (part "RT9013-33GB"))
    )
    (comp (ref "U2") (value "IMU660") (footprint "HDR1X6-M") (libsource (lib "icm20602") (part "ICM20602")))
    (comp (ref "U3") (value "AS1015") (footprint "SOP8_L") (libsource (lib "*") (part "AS1015")))
    (comp (ref "U4")
      (value "RT9013-33GB")
      (footprint "MM32F5277主板封装库:SOT-23-5")
      (fields (field (name "MANUFACTURER") "RICHTEK(台湾立锜)"))
      (libsource (lib "RT9013-33GB") (part "RT9013-33GB"))
    )
    (comp (ref "U5")
      (value "RT9013-33GB")
      (footprint "MM32F5277主板封装库:SOT-23-5")
      (fields (field (name "MANUFACTURER") "RICHTEK(台湾立锜)"))
      (libsource (lib "RT9013-33GB") (part "RT9013-33GB"))
    )
    (comp (ref "U6") (value "ADUM1200") (footprint "SOP8_L") (libsource (lib "20170112") (part "ADUM1201")))
    (comp (ref "U7")
      (value "RT9013-33GB")
      (footprint "MM32F5277主板封装库:SOT-23-5")
      (fields (field (name "MANUFACTURER") "RICHTEK(台湾立锜)"))
      (libsource (lib "RT9013-33GB") (part "RT9013-33GB"))
    )
    (comp (ref "U8")
      (value "TPS63070RNMR")
      (footprint "VQFN-HR-15_L3.0-W2.5-P0.50-BL_TPS63070RNMR")
      (fields (field (name "MANUFACTURER") "TI(德州仪器)"))
      (libsource (lib "TPS63070RNMR") (part "TPS63070RNMR"))
    )
    (comp (ref "UU1") (value "ADUM1200") (footprint "SOP8_L") (libsource (lib "20170112") (part "ADUM1201")))
    (comp (ref "WIFI1")
      (value "无线串口1")
      (footprint "HDR2.54-LI-2x4P")
      (libsource (lib "插件") (part "HEADER2X4"))
    )
    (comp (ref "WIFI2")
      (value "无线串口2")
      (footprint "HDR2.54-LI-2x4P")
      (libsource (lib "插件") (part "HEADER2X4"))
    )
    (comp (ref "X1")
      (value "7pF  32.768K")
      (footprint "OSC 3215-2P")
      (fields
        (field (name "MANUFACTURER") "Seiko(精工)")
        (field (name "MANUFACTURER PART") "SC-32S32.768kHz20PPM12.5pF")
      )
      (libsource (lib "altium-import") (part "root_2_SC-32S32.768kHz20PPM12.5pF_"))
    )
    (comp (ref "X2")
      (value "20pF 12MHz")
      (footprint "X3225-4")
      (description "12MHZ")
      (fields (field (name "MANUFACTURER") "YXC扬兴科技") (field (name "MANUFACTURER PART") "X32258MSB4SI"))
      (libsource (lib "X32258MSB4SI1_X32258MSB4SI") (part "X32258MSB4SI"))
    )
  )
  (nets
    (net (code "1") (name "/ADC0") (class "Default")
      (node (ref "*1") (pin "34") (pinfunction "PA0_34") (pintype "passive"))
      (node (ref "JP3") (pin "5") (pinfunction "5_5") (pintype "passive"))
    )
    (net (code "2") (name "/ADC1") (class "Default")
      (node (ref "*1") (pin "35") (pinfunction "PA1_35") (pintype "passive"))
      (node (ref "JP3") (pin "6") (pinfunction "6_6") (pintype "passive"))
    )
    (net (code "3") (name "/ADC2") (class "Default")
      (node (ref "*1") (pin "36") (pinfunction "PA2_36") (pintype "passive"))
      (node (ref "JP3") (pin "9") (pinfunction "9_9") (pintype "passive"))
    )
    (net (code "4") (name "/ADC3") (class "Default")
      (node (ref "*1") (pin "37") (pinfunction "PA3_37") (pintype "passive"))
      (node (ref "JP3") (pin "10") (pinfunction "10_10") (pintype "passive"))
    )
    (net (code "5") (name "/ADC4") (class "Default")
      (node (ref "*1") (pin "40") (pinfunction "PA4_40") (pintype "passive"))
      (node (ref "JP3") (pin "4") (pinfunction "4_4") (pintype "passive"))
    )
    (net (code "6") (name "/ADC5") (class "Default")
      (node (ref "*1") (pin "41") (pinfunction "PA5_41") (pintype "passive"))
      (node (ref "JP3") (pin "3") (pinfunction "3_3") (pintype "passive"))
    )
    (net (code "7") (name "/ADC6") (class "Default")
      (node (ref "*1") (pin "42") (pinfunction "PA6_42") (pintype "passive"))
      (node (ref "JP3") (pin "2") (pinfunction "2_2") (pintype "passive"))
    )
    (net (code "8") (name "/ADC7") (class "Default")
      (node (ref "*1") (pin "43") (pinfunction "PA7_43") (pintype "passive"))
      (node (ref "JP3") (pin "1") (pinfunction "1_1") (pintype "passive"))
    )
    (net (code "9") (name "/ADCP") (class "Default")
      (node (ref "*1") (pin "22") (pinfunction "PF10_22") (pintype "passive"))
      (node (ref "C41") (pin "2") (pinfunction "2_2") (pintype "passive"))
      (node (ref "R38") (pin "2") (pinfunction "2_2") (pintype "passive"))
      (node (ref "R40") (pin "1") (pinfunction "1_1") (pintype "passive"))
    )
    (net (code "10") (name "/BAT") (class "Default")
      (node (ref "MOTO1") (pin "2") (pinfunction "2_2") (pintype "passive"))
      (node (ref "S6") (pin "1") (pintype "passive"))
    )
    (net (code "11") (name "/BEEP_E3") (class "Default")
      (node (ref "*1") (pin "134") (pinfunction "PB4_134") (pintype "passive"))
      (node (ref "R6") (pin "1") (pinfunction "1_1") (pintype "passive"))
    )
    (net (code "12") (name "/BOOT0") (class "Default")
      (node (ref "*1") (pin "138") (pinfunction "PH3_138") (pintype "passive"))
      (node (ref "R20") (pin "2") (pinfunction "2_2") (pintype "passive"))
      (node (ref "S1") (pin "1") (pinfunction "1_1") (pintype "passive"))
    )
    (net (code "13") (name "/D0") (class "Default")
      (node (ref "*1") (pin "56") (pinfunction "PG0_56") (pintype "passive"))
      (node (ref "JP1") (pin "16") (pinfunction "16_16") (pintype "passive"))
    )
    (net (code "14") (name "/D1") (class "Default")
      (node (ref "*1") (pin "57") (pinfunction "PG1_57") (pintype "passive"))
      (node (ref "JP1") (pin "14") (pinfunction "14_14") (pintype "passive"))
    )
    (net (code "15") (name "/D2") (class "Default")
      (node (ref "*1") (pin "87") (pinfunction "PG2_87") (pintype "passive"))
      (node (ref "JP1") (pin "12") (pinfunction "12_12") (pintype "passive"))
    )
    (net (code "16") (name "/D3") (class "Default")
      (node (ref "*1") (pin "88") (pinfunction "PG3_88") (pintype "passive"))
      (node (ref "JP1") (pin "10") (pinfunction "10_10") (pintype "passive"))
    )
    (net (code "17") (name "/D4") (class "Default")
      (node (ref "*1") (pin "89") (pinfunction "PG4_89") (pintype "passive"))
      (node (ref "JP1") (pin "8") (pinfunction "8_8") (pintype "passive"))
    )
    (net (code "18") (name "/D5") (class "Default")
      (node (ref "*1") (pin "90") (pinfunction "PG5_90") (pintype "passive"))
      (node (ref "JP1") (pin "6") (pinfunction "6_6") (pintype "passive"))
    )
    (net (code "19") (name "/D6") (class "Default")
      (node (ref "*1") (pin "91") (pinfunction "PG6_91") (pintype "passive"))
      (node (ref "JP1") (pin "4") (pinfunction "4_4") (pintype "passive"))
    )
    (net (code "20") (name "/D7") (class "Default")
      (node (ref "*1") (pin "92") (pinfunction "PG7_92") (pintype "passive"))
      (node (ref "JP1") (pin "2") (pinfunction "2_2") (pintype "passive"))
    )
    (net (code "21") (name "/DVP_PLCK") (class "Default")
      (node (ref "*1") (pin "58") (pinfunction "PE7_58") (pintype "passive"))
      (node (ref "JP1") (pin "15") (pinfunction "15_15") (pintype "passive"))
    )
    (net (code "22") (name "/DVP_VSYNC") (class "Default")
      (node (ref "*1") (pin "59") (pinfunction "PE8_59") (pintype "passive"))
      (node (ref "JP1") (pin "5") (pinfunction "5_5") (pintype "passive"))
    )
    (net (code "23") (name "/ICM_CS") (class "Default")
      (node (ref "*1") (pin "73") (pinfunction "PB12_73") (pintype "passive"))
      (node (ref "U2") (pin "6") (pinfunction "CS_6") (pintype "passive"))
    )
    (net (code "24") (name "/ICM_SAO") (class "Default")
      (node (ref "*1") (pin "75") (pinfunction "PB14_75") (pintype "passive"))
      (node (ref "U2") (pin "5") (pinfunction "SDO_5") (pintype "passive"))
    )
    (net (code "25") (name "/ICM_SCL") (class "Default")
      (node (ref "*1") (pin "74") (pinfunction "PB13_74") (pintype "passive"))
      (node (ref "U2") (pin "3") (pinfunction "SPC_3") (pintype "passive"))
    )
    (net (code "26") (name "/ICM_SDA") (class "Default")
      (node (ref "*1") (pin "76") (pinfunction "PB15_76") (pintype "passive"))
      (node (ref "U2") (pin "4") (pinfunction "SDI_4") (pintype "passive"))
    )
    (net (code "27") (name "/IO1") (class "Default")
      (node (ref "*1") (pin "64") (pinfunction "PE11_64") (pintype "passive"))
      (node (ref "IO1") (pin "1") (pinfunction "1_1") (pintype "passive"))
    )
    (net (code "28") (name "/IO2") (class "Default")
      (node (ref "*1") (pin "66") (pinfunction "PE13_66") (pintype "passive"))
      (node (ref "IO1") (pin "2") (pinfunction "2_2") (pintype "passive"))
    )
    (net (code "29") (name "/IPS0") (class "Default")
      (node (ref "*1") (pin "123") (pinfunction "PD7_123") (pintype "passive"))
      (node (ref "IPS1") (pin "1") (pinfunction "1_1") (pintype "passive"))
    )
    (net (code "30") (name "/IPS1") (class "Default")
      (node (ref "*1") (pin "122") (pinfunction "PD6_122") (pintype "passive"))
      (node (ref "IPS1") (pin "3") (pinfunction "3_3") (pintype "passive"))
    )
    (net (code "31") (name "/IPS2") (class "Default")
      (node (ref "*1") (pin "119") (pinfunction "PD5_119") (pintype "passive"))
      (node (ref "IPS1") (pin "5") (pinfunction "5_5") (pintype "passive"))
    )
    (net (code "32") (name "/IPS3") (class "Default")
      (node (ref "*1") (pin "118") (pinfunction "PD4_118") (pintype "passive"))
      (node (ref "IPS1") (pin "7") (pinfunction "7_7") (pintype "passive"))
    )
    (net (code "33") (name "/IPS4") (class "Default")
      (node (ref "*1") (pin "117") (pinfunction "PD3_117") (pintype "passive"))
      (node (ref "IPS1") (pin "9") (pinfunction "9_9") (pintype "passive"))
    )
    (net (code "34") (name "/IPS5") (class "Default")
      (node (ref "*1") (pin "116") (pinfunction "PD2_116") (pintype "passive"))
      (node (ref "IPS1") (pin "11") (pinfunction "11_11") (pintype "passive"))
    )
    (net (code "35") (name "/IPS6") (class "Default")
      (node (ref "*1") (pin "115") (pinfunction "PD1_115") (pintype "passive"))
      (node (ref "IPS1") (pin "13") (pinfunction "13_13") (pintype "passive"))
    )
    (net (code "36") (name "/IPS7") (class "Default")
      (node (ref "*1") (pin "114") (pinfunction "PD0_114") (pintype "passive"))
      (node (ref "IPS1") (pin "15") (pinfunction "15_15") (pintype "passive"))
    )
    (net (code "37") (name "/IPS_BL") (class "Default")
      (node (ref "*1") (pin "103") (pinfunction "PA11_103") (pintype "passive"))
      (node (ref "IPS1") (pin "16") (pinfunction "16_16") (pintype "passive"))
    )
    (net (code "38") (name "/IPS_CS") (class "Default")
      (node (ref "*1") (pin "104") (pinfunction "PA12_104") (pintype "passive"))
      (node (ref "IPS1") (pin "14") (pinfunction "14_14") (pintype "passive"))
    )
    (net (code "39") (name "/IPS_RD") (class "Default")
      (node (ref "*1") (pin "113") (pinfunction "PC12_113") (pintype "passive"))
      (node (ref "IPS1") (pin "6") (pinfunction "6_6") (pintype "passive"))
    )
    (net (code "40") (name "/IPS_RS") (class "Default")
      (node (ref "*1") (pin "111") (pinfunction "PC10_111") (pintype "passive"))
      (node (ref "IPS1") (pin "10") (pinfunction "10_10") (pintype "passive"))
    )
    (net (code "41") (name "/IPS_RST") (class "Default")
      (node (ref "*1") (pin "106") (pinfunction "PH2_106") (pintype "passive"))
      (node (ref "IPS1") (pin "12") (pinfunction "12_12") (pintype "passive"))
    )
    (net (code "42") (name "/IPS_WR") (class "Default")
      (node (ref "*1") (pin "112") (pinfunction "PC11_112") (pintype "passive"))
      (node (ref "IPS1") (pin "8") (pinfunction "8_8") (pintype "passive"))
    )
    (net (code "43") (name "/KEY1") (class "Default")
      (node (ref "*1") (pin "55") (pinfunction "PF15_55") (pintype "passive"))
      (node (ref "R29") (pin "1") (pinfunction "1_1") (pintype "passive"))
    )
    (net (code "44") (name "/KEY2") (class "Default")
      (node (ref "*1") (pin "54") (pinfunction "PF14_54") (pintype "passive"))
      (node (ref "R30") (pin "1") (pinfunction "1_1") (pintype "passive"))
    )
    (net (code "45") (name "/KEY3") (class "Default")
      (node (ref "*1") (pin "53") (pinfunction "PF13_53") (pintype "passive"))
      (node (ref "R33") (pin "1") (pinfunction "1_1") (pintype "passive"))
    )
    (net (code "46") (name "/KEY4") (class "Default")
      (node (ref "*1") (pin "49") (pinfunction "PF11_49") (pintype "passive"))
      (node (ref "R34") (pin "1") (pinfunction "1_1") (pintype "passive"))
    )
    (net (code "47") (name "/KEY5") (class "Default")
      (node (ref "*1") (pin "48") (pinfunction "PB2_48") (pintype "passive"))
      (node (ref "R39") (pin "1") (pinfunction "1_1") (pintype "passive"))
    )
    (net (code "48") (name "/OSC32_I") (class "Default")
      (node (ref "*1") (pin "8") (pinfunction "PC14_8") (pintype "passive"))
      (node (ref "C13") (pin "2") (pinfunction "2_2") (pintype "passive"))
      (node (ref "X1") (pin "1") (pinfunction "1_1") (pintype "passive"))
    )
    (net (code "49") (name "/OSC32_O") (class "Default")
      (node (ref "*1") (pin "9") (pinfunction "PC15_9") (pintype "passive"))
      (node (ref "C12") (pin "2") (pinfunction "2_2") (pintype "passive"))
      (node (ref "X1") (pin "2") (pinfunction "2_2") (pintype "passive"))
    )
    (net (code "50") (name "/OSC_IN") (class "Default")
      (node (ref "*1") (pin "23") (pinfunction "PH0_23") (pintype "passive"))
      (node (ref "C20") (pin "2") (pinfunction "2_2") (pintype "passive"))
      (node (ref "R8") (pin "2") (pinfunction "2_2") (pintype "passive"))
      (node (ref "X2") (pin "3") (pinfunction "3_3") (pintype "passive"))
    )
    (net (code "51") (name "/OSC_OUT") (class "Default")
      (node (ref "*1") (pin "24") (pinfunction "PH1_24") (pintype "passive"))
      (node (ref "R8") (pin "1") (pinfunction "1_1") (pintype "passive"))
      (node (ref "R9") (pin "2") (pinfunction "2_2") (pintype "passive"))
    )
    (net (code "52") (name "/PA9") (class "Default")
      (node (ref "*1") (pin "101") (pinfunction "PA9_101") (pintype "passive"))
      (node (ref "R1") (pin "1") (pinfunction "1_1") (pintype "passive"))
    )
    (net (code "53") (name "/PA10") (class "Default")
      (node (ref "*1") (pin "102") (pinfunction "PA10_102") (pintype "passive"))
      (node (ref "R3") (pin "1") (pinfunction "1_1") (pintype "passive"))
    )
    (net (code "54") (name "/PWM1") (class "Default")
      (node (ref "H2") (pin "1") (pinfunction "1_1") (pintype "passive"))
      (node (ref "UU1") (pin "6") (pinfunction "VOB_6") (pintype "passive"))
    )
    (net (code "55") (name "/PWM2") (class "Default")
      (node (ref "H2") (pin "2") (pinfunction "2_2") (pintype "passive"))
      (node (ref "UU1") (pin "7") (pinfunction "VOA_7") (pintype "passive"))
    )
    (net (code "56") (name "/PWM3") (class "Default")
      (node (ref "H1") (pin "1") (pinfunction "1_1") (pintype "passive"))
      (node (ref "U6") (pin "6") (pinfunction "VOB_6") (pintype "passive"))
    )
    (net (code "57") (name "/PWM4") (class "Default")
      (node (ref "H1") (pin "2") (pinfunction "2_2") (pintype "passive"))
      (node (ref "U6") (pin "7") (pinfunction "VOA_7") (pintype "passive"))
    )
    (net (code "58") (name "/RST") (class "Default")
      (node (ref "*1") (pin "25") (pinfunction "nRST_25") (pintype "passive"))
      (node (ref "C25") (pin "2") (pinfunction "2_2") (pintype "passive"))
      (node (ref "JP2") (pin "10") (pinfunction "10_10") (pintype "passive"))
      (node (ref "R21") (pin "1") (pinfunction "1_1") (pintype "passive"))
      (node (ref "S2") (pin "2") (pinfunction "2_2") (pintype "passive"))
    )
    (net (code "59") (name "/RTS1") (class "Default")
      (node (ref "*1") (pin "128") (pinfunction "PG13_128") (pintype "passive"))
      (node (ref "WIFI2") (pin "4") (pinfunction "4_4") (pintype "power_in"))
    )
    (net (code "60") (name "/RTS2") (class "Default")
      (node (ref "*1") (pin "4") (pinfunction "PE5_4") (pintype "passive"))
      (node (ref "WIFI1") (pin "4") (pinfunction "4_4") (pintype "power_in"))
    )
    (net (code "61") (name "/SW1") (class "Default")
      (node (ref "*1") (pin "47") (pinfunction "PB1_47") (pintype "passive"))
      (node (ref "R11") (pin "1") (pinfunction "1_1") (pintype "passive"))
    )
    (net (code "62") (name "/SW2") (class "Default")
      (node (ref "*1") (pin "46") (pinfunction "PB0_46") (pintype "passive"))
      (node (ref "R12") (pin "1") (pinfunction "1_1") (pintype "passive"))
    )
    (net (code "63") (name "/SW3") (class "Default")
      (node (ref "*1") (pin "45") (pinfunction "PC5_45") (pintype "passive"))
      (node (ref "R13") (pin "1") (pinfunction "1_1") (pintype "passive"))
    )
    (net (code "64") (name "/SW4") (class "Default")
      (node (ref "*1") (pin "44") (pinfunction "PC4_44") (pintype "passive"))
      (node (ref "R15") (pin "1") (pinfunction "1_1") (pintype "passive"))
    )
    (net (code "65") (name "/SWCLK") (class "Default")
      (node (ref "*1") (pin "109") (pinfunction "PA14_109") (pintype "passive"))
      (node (ref "JP2") (pin "4") (pinfunction "4_4") (pintype "passive"))
    )
    (net (code "66") (name "/SWDIO") (class "Default")
      (node (ref "*1") (pin "105") (pinfunction "PA13_105") (pintype "passive"))
      (node (ref "JP2") (pin "2") (pinfunction "2_2") (pintype "passive"))
    )
    (net (code "67") (name "/TIM2_CH2") (class "Default")
      (node (ref "*1") (pin "110") (pinfunction "PA15_110") (pintype "passive"))
      (node (ref "R5") (pin "1") (pinfunction "1_1") (pintype "passive"))
    )
    (net (code "68") (name "/TIM3_ENC1") (class "Default")
      (node (ref "*1") (pin "1") (pinfunction "PE2_1") (pintype "passive"))
      (node (ref "mini*1") (pin "2") (pinfunction "2_2") (pintype "passive"))
    )
    (net (code "69") (name "/TIM3_ENC2") (class "Default")
      (node (ref "*1") (pin "2") (pinfunction "PE3_2") (pintype "passive"))
      (node (ref "mini*1") (pin "5") (pinfunction "5_5") (pintype "passive"))
    )
    (net (code "70") (name "/TIM4_ENC1") (class "Default")
      (node (ref "*1") (pin "136") (pinfunction "PB6_136") (pintype "passive"))
      (node (ref "mini1") (pin "2") (pinfunction "2_2") (pintype "passive"))
    )
    (net (code "71") (name "/TIM4_ENC2") (class "Default")
      (node (ref "*1") (pin "137") (pinfunction "PB7_137") (pintype "passive"))
      (node (ref "mini1") (pin "5") (pinfunction "5_5") (pintype "passive"))
    )
    (net (code "72") (name "/TIM5_CH1") (class "Default")
      (node (ref "*1") (pin "18") (pinfunction "PF6_18") (pintype "passive"))
      (node (ref "R32") (pin "1") (pinfunction "1_1") (pintype "passive"))
    )
    (net (code "73") (name "/TIM5_CH2") (class "Default")
      (node (ref "*1") (pin "19") (pinfunction "PF7_19") (pintype "passive"))
      (node (ref "R31") (pin "1") (pinfunction "1_1") (pintype "passive"))
    )
    (net (code "74") (name "/TIM5_CH3") (class "Default")
      (node (ref "*1") (pin "20") (pinfunction "PF8_20") (pintype "passive"))
      (node (ref "R23") (pin "1") (pinfunction "1_1") (pintype "passive"))
    )
    (net (code "75") (name "/TIM5_CH4") (class "Default")
      (node (ref "*1") (pin "21") (pinfunction "PF9_21") (pintype "passive"))
      (node (ref "R22") (pin "1") (pinfunction "1_1") (pintype "passive"))
    )
    (net (code "76") (name "/TOF_RST") (class "Default")
      (node (ref "*1") (pin "68") (pinfunction "PE15_68") (pintype "passive"))
      (node (ref "P1") (pin "5") (pinfunction "5_5") (pintype "passive"))
    )
    (net (code "77") (name "/TOF_SCL") (class "Default")
      (node (ref "*1") (pin "69") (pinfunction "PB10_69") (pintype "passive"))
      (node (ref "R2") (pin "1") (pinfunction "1_1") (pintype "passive"))
    )
    (net (code "78") (name "/TOF_SDA") (class "Default")
      (node (ref "*1") (pin "70") (pinfunction "PB11_70") (pintype "passive"))
      (node (ref "P1") (pin "4") (pinfunction "4_4") (pintype "passive"))
    )
    (net (code "79") (name "/UART3_RX") (class "Default")
      (node (ref "*1") (pin "78") (pinfunction "PD9_78") (pintype "passive"))
      (node (ref "JP1") (pin "11") (pinfunction "11_11") (pintype "passive"))
    )
    (net (code "80") (name "/UART3_TX") (class "Default")
      (node (ref "*1") (pin "77") (pinfunction "PD8_77") (pintype "passive"))
      (node (ref "JP1") (pin "9") (pinfunction "9_9") (pintype "passive"))
    )
    (net (code "81") (name "/UART4_RX") (class "Default")
      (node (ref "*1") (pin "27") (pinfunction "PC1_27") (pintype "passive"))
      (node (ref "WIFI1") (pin "3") (pinfunction "3_3") (pintype "power_in"))
    )
    (net (code "82") (name "/UART4_TX") (class "Default")
      (node (ref "*1") (pin "26") (pinfunction "PC0_26") (pintype "passive"))
      (node (ref "WIFI1") (pin "1") (pinfunction "1_1") (pintype "passive"))
    )
    (net (code "83") (name "/UART6_RX") (class "Default")
      (node (ref "*1") (pin "124") (pinfunction "PG9_124") (pintype "passive"))
      (node (ref "WIFI2") (pin "3") (pinfunction "3_3") (pintype "power_in"))
    )
    (net (code "84") (name "/UART6_TX") (class "Default")
      (node (ref "*1") (pin "129") (pinfunction "PG14_129") (pintype "passive"))
      (node (ref "WIFI2") (pin "1") (pinfunction "1_1") (pintype "passive"))
    )
    (net (code "85") (name "3.3V") (class "Default")
      (node (ref "C26") (pin "2") (pinfunction "2_2") (pintype "passive"))
      (node (ref "C29") (pin "1") (pinfunction "1_1") (pintype "passive"))
      (node (ref "J1") (pin "2") (pinfunction "2_2") (pintype "passive"))
      (node (ref "P1") (pin "1") (pinfunction "1_1") (pintype "passive"))
      (node (ref "Q1") (pin "3") (pinfunction "E_3") (pintype "passive"))
      (node (ref "R24") (pin "1") (pinfunction "1_1") (pintype "passive"))
      (node (ref "R25") (pin "1") (pinfunction "1_1") (pintype "passive"))
      (node (ref "R26") (pin "1") (pinfunction "1_1") (pintype "passive"))
      (node (ref "R27") (pin "1") (pinfunction "1_1") (pintype "passive"))
      (node (ref "R28") (pin "1") (pinfunction "1_1") (pintype "passive"))
      (node (ref "R42") (pin "1") (pinfunction "1_1") (pintype "passive"))
      (node (ref "U2") (pin "1") (pinfunction "VCC_1") (pintype "passive"))
      (node (ref "U4") (pin "5") (pinfunction "VOUT_5") (pintype "passive"))
      (node (ref "mini*1") (pin "4") (pinfunction "4_4") (pintype "passive"))
      (node (ref "mini1") (pin "4") (pinfunction "4_4") (pintype "passive"))
    )
    (net (code "86") (name "5V") (class "Default")
      (node (ref "C27") (pin "1") (pinfunction "1_1") (pintype "passive"))
      (node (ref "C28") (pin "2") (pinfunction "2_2") (pintype "passive"))
      (node (ref "C31") (pin "1") (pinfunction "1_1") (pintype "passive"))
      (node (ref "C32") (pin "2") (pinfunction "2_2") (pintype "passive"))
      (node (ref "C37") (pin "1") (pinfunction "1_1") (pintype "passive"))
      (node (ref "C38") (pin "2") (pinfunction "2_2") (pintype "passive"))
      (node (ref "C48") (pin "2") (pinfunction "2_2") (pintype "passive"))
      (node (ref "C49") (pin "1") (pinfunction "1_1") (pintype "passive"))
      (node (ref "C50") (pin "2") (pinfunction "2_2") (pintype "passive"))
      (node (ref "C51") (pin "2") (pinfunction "2_2") (pintype "passive"))
      (node (ref "D4") (pin "A") (pinfunction "A_A") (pintype "passive"))
      (node (ref "IPS1") (pin "4") (pinfunction "4_4") (pintype "passive"))
      (node (ref "J1") (pin "1") (pinfunction "1_1") (pintype "passive"))
      (node (ref "R37") (pin "1") (pinfunction "1_1") (pintype "passive"))
      (node (ref "R43") (pin "1") (pinfunction "1_1") (pintype "passive"))
      (node (ref "R44") (pin "1") (pinfunction "1_1") (pintype "passive"))
      (node (ref "U4") (pin "1") (pinfunction "VIN_1") (pintype "passive"))
      (node (ref "U4") (pin "3") (pinfunction "EN_3") (pintype "passive"))
      (node (ref "U5") (pin "1") (pinfunction "VIN_1") (pintype "passive"))
      (node (ref "U5") (pin "3") (pinfunction "EN_3") (pintype "passive"))
      (node (ref "U6") (pin "1") (pinfunction "VDD1_1") (pintype "passive"))
      (node (ref "U6") (pin "8") (pinfunction "VDD2_8") (pintype "passive"))
      (node (ref "U7") (pin "1") (pinfunction "VIN_1") (pintype "passive"))
      (node (ref "U7") (pin "3") (pinfunction "EN_3") (pintype "passive"))
      (node (ref "U8") (pin "7") (pinfunction "Vout_7") (pintype "passive"))
      (node (ref "U8") (pin "8") (pinfunction "Vout_8") (pintype "passive"))
      (node (ref "UU1") (pin "1") (pinfunction "VDD1_1") (pintype "passive"))
      (node (ref "UU1") (pin "8") (pinfunction "VDD2_8") (pintype "passive"))
      (node (ref "WIFI1") (pin "7") (pinfunction "7_7") (pintype "power_in"))
      (node (ref "WIFI2") (pin "7") (pinfunction "7_7") (pintype "power_in"))
    )
    (net (code "87") (name "6V") (class "Default")
      (node (ref "C23") (pin "1") (pinfunction "1_1") (pintype "passive"))
      (node (ref "C24") (pin "1") (pinfunction "1_1") (pintype "passive"))
      (node (ref "L1") (pin "2") (pinfunction "2_2") (pintype "passive"))
      (node (ref "P2") (pin "2") (pinfunction "2_2") (pintype "passive"))
      (node (ref "R17") (pin "1") (pinfunction "1_1") (pintype "passive"))
      (node (ref "R18") (pin "2") (pinfunction "2_2") (pintype "passive"))
    )
    (net (code "88") (name "Cam3.3V") (class "Default")
      (node (ref "C36") (pin "2") (pinfunction "2_2") (pintype "passive"))
      (node (ref "C39") (pin "1") (pinfunction "1_1") (pintype "passive"))
      (node (ref "JP1") (pin "1") (pinfunction "1_1") (pintype "passive"))
      (node (ref "U7") (pin "5") (pinfunction "VOUT_5") (pintype "passive"))
    )
    (net (code "89") (name "Core3.3") (class "Default")
      (node (ref "*1") (pin "108") (pinfunction "VDD_108") (pintype "passive"))
      (node (ref "*1") (pin "121") (pinfunction "VDD_121") (pintype "passive"))
      (node (ref "*1") (pin "131") (pinfunction "VDD_131") (pintype "passive"))
      (node (ref "*1") (pin "144") (pinfunction "VDD_144") (pintype "passive"))
      (node (ref "*1") (pin "17") (pinfunction "VDD_17") (pintype "passive"))
      (node (ref "*1") (pin "39") (pinfunction "VDD_39") (pintype "passive"))
      (node (ref "*1") (pin "52") (pinfunction "VDD_52") (pintype "passive"))
      (node (ref "*1") (pin "62") (pinfunction "VDD_62") (pintype "passive"))
      (node (ref "*1") (pin "72") (pinfunction "VDD_72") (pintype "passive"))
      (node (ref "*1") (pin "83") (pinfunction "VSS_83") (pintype "passive"))
      (node (ref "C10") (pin "2") (pinfunction "2_2") (pintype "passive"))
      (node (ref "C11") (pin "2") (pinfunction "2_2") (pintype "passive"))
      (node (ref "C14") (pin "2") (pinfunction "2_2") (pintype "passive"))
      (node (ref "C15") (pin "2") (pinfunction "2_2") (pintype "passive"))
      (node (ref "C16") (pin "2") (pinfunction "2_2") (pintype "passive"))
      (node (ref "C17") (pin "2") (pinfunction "2_2") (pintype "passive"))
      (node (ref "C18") (pin "2") (pinfunction "2_2") (pintype "passive"))
      (node (ref "C2") (pin "2") (pinfunction "2_2") (pintype "passive"))
      (node (ref "C3") (pin "2") (pinfunction "2_2") (pintype "passive"))
      (node (ref "C4") (pin "2") (pinfunction "2_2") (pintype "passive"))
      (node (ref "C5") (pin "2") (pinfunction "2_2") (pintype "passive"))
      (node (ref "C8") (pin "2") (pinfunction "2_2") (pintype "passive"))
      (node (ref "C9") (pin "2") (pinfunction "2_2") (pintype "passive"))
      (node (ref "D1") (pin "A") (pinfunction "A_A") (pintype "passive"))
      (node (ref "D2") (pin "A") (pinfunction "A_A") (pintype "passive"))
      (node (ref "D3") (pin "2") (pinfunction "A_2") (pintype "passive"))
      (node (ref "FB1") (pin "2") (pinfunction "2_2") (pintype "passive"))
      (node (ref "JP2") (pin "1") (pinfunction "1_1") (pintype "passive"))
      (node (ref "R10") (pin "1") (pinfunction "1_1") (pintype "passive"))
      (node (ref "R21") (pin "2") (pinfunction "2_2") (pintype "passive"))
      (node (ref "R4") (pin "1") (pinfunction "1_1") (pintype "passive"))
      (node (ref "S1") (pin "2") (pinfunction "2_2") (pintype "passive"))
      (node (ref "U1") (pin "5") (pinfunction "VOUT_5") (pintype "passive"))
    )
    (net (code "90") (name "GND") (class "Default")
      (node (ref "*1") (pin "107") (pinfunction "VSS_107") (pintype "passive"))
      (node (ref "*1") (pin "120") (pinfunction "VSS_120") (pintype "passive"))
      (node (ref "*1") (pin "130") (pinfunction "VSS_130") (pintype "passive"))
      (node (ref "*1") (pin "143") (pinfunction "VSS_143") (pintype "passive"))
      (node (ref "*1") (pin "16") (pinfunction "VSS_16") (pintype "passive"))
      (node (ref "*1") (pin "31") (pinfunction "VREF-_31") (pintype "passive"))
      (node (ref "*1") (pin "38") (pinfunction "VSS_38") (pintype "passive"))
      (node (ref "*1") (pin "51") (pinfunction "VSS_51") (pintype "passive"))
      (node (ref "*1") (pin "61") (pinfunction "VSS_61") (pintype "passive"))
      (node (ref "*1") (pin "71") (pinfunction "VSS_71") (pintype "passive"))
      (node (ref "*1") (pin "84") (pinfunction "VDD_84") (pintype "passive"))
      (node (ref "C1") (pin "2") (pinfunction "2_2") (pintype "passive"))
      (node (ref "C10") (pin "1") (pinfunction "1_1") (pintype "passive"))
      (node (ref "C11") (pin "1") (pinfunction "1_1") (pintype "passive"))
      (node (ref "C12") (pin "1") (pinfunction "1_1") (pintype "passive"))
      (node (ref "C13") (pin "1") (pinfunction "1_1") (pintype "passive"))
      (node (ref "C14") (pin "1") (pinfunction "1_1") (pintype "passive"))
      (node (ref "C15") (pin "1") (pinfunction "1_1") (pintype "passive"))
      (node (ref "C16") (pin "1") (pinfunction "1_1") (pintype "passive"))
      (node (ref "C17") (pin "1") (pinfunction "1_1") (pintype "passive"))
      (node (ref "C18") (pin "1") (pinfunction "1_1") (pintype "passive"))
      (node (ref "C19") (pin "1") (pinfunction "1_1") (pintype "passive"))
      (node (ref "C2") (pin "1") (pinfunction "1_1") (pintype "passive"))
      (node (ref "C20") (pin "1") (pinfunction "1_1") (pintype "passive"))
      (node (ref "C21") (pin "2") (pinfunction "2_2") (pintype "passive"))
      (node (ref "C22") (pin "2") (pinfunction "2_2") (pintype "passive"))
      (node (ref "C23") (pin "2") (pinfunction "2_2") (pintype "passive"))
      (node (ref "C24") (pin "2") (pinfunction "2_2") (pintype "passive"))
      (node (ref "C25") (pin "1") (pinfunction "1_1") (pintype "passive"))
      (node (ref "C26") (pin "1") (pinfunction "1_1") (pintype "passive"))
      (node (ref "C27") (pin "2") (pinfunction "2_2") (pintype "passive"))
      (node (ref "C28") (pin "1") (pinfunction "1_1") (pintype "passive"))
      (node (ref "C29") (pin "2") (pinfunction "2_2") (pintype "passive"))
      (node (ref "C3") (pin "1") (pinfunction "1_1") (pintype "passive"))
      (node (ref "C30") (pin "1") (pinfunction "1_1") (pintype "passive"))
      (node (ref "C31") (pin "2") (pinfunction "2_2") (pintype "passive"))
      (node (ref "C32") (pin "1") (pinfunction "1_1") (pintype "passive"))
      (node (ref "C33") (pin "2") (pinfunction "2_2") (pintype "passive"))
      (node (ref "C34") (pin "1") (pinfunction "1_1") (pintype "passive"))
      (node (ref "C35") (pin "1") (pinfunction "1_1") (pintype "passive"))
      (node (ref "C36") (pin "1") (pinfunction "1_1") (pintype "passive"))
      (node (ref "C37") (pin "2") (pinfunction "2_2") (pintype "passive"))
      (node (ref "C38") (pin "1") (pinfunction "1_1") (pintype "passive"))
      (node (ref "C39") (pin "2") (pinfunction "2_2") (pintype "passive"))
      (node (ref "C4") (pin "1") (pinfunction "1_1") (pintype "passive"))
      (node (ref "C40") (pin "1") (pinfunction "1_1") (pintype "passive"))
      (node (ref "C41") (pin "1") (pinfunction "1_1") (pintype "passive"))
      (node (ref "C42") (pin "1") (pinfunction "1_1") (pintype "passive"))
      (node (ref "C43") (pin "1") (pinfunction "1_1") (pintype "passive"))
      (node (ref "C44") (pin "1") (pinfunction "1_1") (pintype "passive"))
      (node (ref "C45") (pin "1") (pinfunction "1_1") (pintype "passive"))
      (node (ref "C46") (pin "1") (pinfunction "1_1") (pintype "passive"))
      (node (ref "C47") (pin "1") (pinfunction "1_1") (pintype "passive"))
      (node (ref "C48") (pin "1") (pinfunction "1_1") (pintype "passive"))
      (node (ref "C49") (pin "2") (pinfunction "2_2") (pintype "passive"))
      (node (ref "C5") (pin "1") (pinfunction "1_1") (pintype "passive"))
      (node (ref "C50") (pin "1") (pinfunction "1_1") (pintype "passive"))
      (node (ref "C51") (pin "1") (pinfunction "1_1") (pintype "passive"))
      (node (ref "C6") (pin "1") (pinfunction "1_1") (pintype "passive"))
      (node (ref "C7") (pin "1") (pinfunction "1_1") (pintype "passive"))
      (node (ref "C8") (pin "1") (pinfunction "1_1") (pintype "passive"))
      (node (ref "C9") (pin "1") (pinfunction "1_1") (pintype "passive"))
      (node (ref "CN1") (pin "2") (pinfunction "2_2") (pintype "passive"))
      (node (ref "D1") (pin "K") (pinfunction "K_K") (pintype "passive"))
      (node (ref "D2") (pin "K") (pinfunction "K_K") (pintype "passive"))
      (node (ref "D5") (pin "1") (pinfunction "A_1") (pintype "passive"))
      (node (ref "E1") (pin "2") (pinfunction "K_2") (pintype "passive"))
      (node (ref "E2") (pin "2") (pinfunction "K_2") (pintype "passive"))
      (node (ref "E3") (pin "2") (pinfunction "K_2") (pintype "passive"))
      (node (ref "IPS1") (pin "2") (pinfunction "2_2") (pintype "passive"))
      (node (ref "J2") (pin "1") (pinfunction "1_1") (pintype "passive"))
      (node (ref "J3") (pin "1") (pinfunction "1_1") (pintype "passive"))
      (node (ref "J4") (pin "1") (pinfunction "1_1") (pintype "passive"))
      (node (ref "JP1") (pin "13") (pinfunction "13_13") (pintype "passive"))
      (node (ref "JP1") (pin "3") (pinfunction "3_3") (pintype "passive"))
      (node (ref "JP2") (pin "3") (pinfunction "3_3") (pintype "passive"))
      (node (ref "JP2") (pin "5") (pinfunction "5_5") (pintype "passive"))
      (node (ref "JP3") (pin "7") (pinfunction "7_7") (pintype "passive"))
      (node (ref "LED1") (pin "2") (pinfunction "2_2") (pintype "passive"))
      (node (ref "LS1") (pin "1") (pinfunction "1_1") (pintype "passive"))
      (node (ref "MOTO1") (pin "1") (pinfunction "1_1") (pintype "passive"))
      (node (ref "P1") (pin "2") (pinfunction "2_2") (pintype "passive"))
      (node (ref "P2") (pin "1") (pinfunction "1_1") (pintype "passive"))
      (node (ref "R14") (pin "2") (pinfunction "2_2") (pintype "passive"))
      (node (ref "R20") (pin "1") (pinfunction "1_1") (pintype "passive"))
      (node (ref "R40") (pin "2") (pinfunction "2_2") (pintype "passive"))
      (node (ref "R41") (pin "2") (pinfunction "2_2") (pintype "passive"))
      (node (ref "S2") (pin "1") (pinfunction "1_1") (pintype "passive"))
      (node (ref "S3") (pin "2") (pinfunction "2_2") (pintype "passive"))
      (node (ref "S5") (pin "2") (pinfunction "2_2") (pintype "passive"))
      (node (ref "S7") (pin "2") (pinfunction "2_2") (pintype "passive"))
      (node (ref "S8") (pin "2") (pinfunction "2_2") (pintype "passive"))
      (node (ref "S9") (pin "2") (pinfunction "2_2") (pintype "passive"))
      (node (ref "SW1") (pin "5") (pinfunction "B4_5") (pintype "passive"))
      (node (ref "SW1") (pin "6") (pinfunction "B3_6") (pintype "passive"))
      (node (ref "SW1") (pin "7") (pinfunction "B2_7") (pintype "passive"))
      (node (ref "SW1") (pin "8") (pinfunction "B1_8") (pintype "passive"))
      (node (ref "Test1") (pin "1") (pinfunction "1_1") (pintype "passive"))
      (node (ref "U1") (pin "2") (pinfunction "GND_2") (pintype "passive"))
      (node (ref "U2") (pin "2") (pinfunction "GND_2") (pintype "passive"))
      (node (ref "U3") (pin "7") (pinfunction "GND_7") (pintype "passive"))
      (node (ref "U3") (pin "8") (pinfunction "GND_8") (pintype "passive"))
      (node (ref "U4") (pin "2") (pinfunction "GND_2") (pintype "passive"))
      (node (ref "U5") (pin "2") (pinfunction "GND_2") (pintype "passive"))
      (node (ref "U6") (pin "4") (pinfunction "GND1_4") (pintype "passive"))
      (node (ref "U6") (pin "5") (pinfunction "GND2_5") (pintype "passive"))
      (node (ref "U7") (pin "2") (pinfunction "GND_2") (pintype "passive"))
      (node (ref "U8") (pin "10") (pinfunction "PGND_10") (pintype "passive"))
      (node (ref "U8") (pin "4") (pinfunction "GND_4") (pintype "passive"))
      (node (ref "U8") (pin "6") (pinfunction "FB2_6") (pintype "passive"))
      (node (ref "UU1") (pin "4") (pinfunction "GND1_4") (pintype "passive"))
      (node (ref "UU1") (pin "5") (pinfunction "GND2_5") (pintype "passive"))
      (node (ref "WIFI1") (pin "5") (pinfunction "5_5") (pintype "power_in"))
      (node (ref "WIFI1") (pin "6") (pinfunction "6_6") (pintype "power_in"))
      (node (ref "WIFI2") (pin "5") (pinfunction "5_5") (pintype "power_in"))
      (node (ref "WIFI2") (pin "6") (pinfunction "6_6") (pintype "power_in"))
      (node (ref "mini*1") (pin "1") (pinfunction "1_1") (pintype "passive"))
      (node (ref "mini1") (pin "1") (pinfunction "1_1") (pintype "passive"))
    )
    (net (code "91") (name "Net-(*1-VBAT)") (class "Default")
      (node (ref "*1") (pin "6") (pinfunction "VBAT_6") (pintype "passive"))
      (node (ref "D3") (pin "1") (pinfunction "K_1") (pintype "passive"))
    )
    (net (code "92") (name "Net-(*1-VDDA)") (class "Default")
      (node (ref "*1") (pin "32") (pinfunction "VREF+_32") (pintype "passive"))
      (node (ref "*1") (pin "33") (pinfunction "VDDA_33") (pintype "passive"))
      (node (ref "C1") (pin "1") (pinfunction "1_1") (pintype "passive"))
      (node (ref "FB1") (pin "1") (pinfunction "1_1") (pintype "passive"))
    )
    (net (code "93") (name "Net-(C19-Pad2)") (class "Default")
      (node (ref "C19") (pin "2") (pinfunction "2_2") (pintype "passive"))
      (node (ref "R9") (pin "1") (pinfunction "1_1") (pintype "passive"))
      (node (ref "X2") (pin "1") (pinfunction "1_1") (pintype "passive"))
    )
    (net (code "94") (name "Net-(C34-Pad2)") (class "Default")
      (node (ref "C34") (pin "2") (pinfunction "2_2") (pintype "passive"))
      (node (ref "R28") (pin "2") (pinfunction "2_2") (pintype "passive"))
      (node (ref "R29") (pin "2") (pinfunction "2_2") (pintype "passive"))
      (node (ref "S3") (pin "1") (pinfunction "1_1") (pintype "passive"))
    )
    (net (code "95") (name "Net-(C35-Pad2)") (class "Default")
      (node (ref "C35") (pin "2") (pinfunction "2_2") (pintype "passive"))
      (node (ref "R27") (pin "2") (pinfunction "2_2") (pintype "passive"))
      (node (ref "R30") (pin "2") (pinfunction "2_2") (pintype "passive"))
      (node (ref "S5") (pin "1") (pinfunction "1_1") (pintype "passive"))
    )
    (net (code "96") (name "Net-(C40-Pad2)") (class "Default")
      (node (ref "C40") (pin "2") (pinfunction "2_2") (pintype "passive"))
      (node (ref "R26") (pin "2") (pinfunction "2_2") (pintype "passive"))
      (node (ref "R33") (pin "2") (pinfunction "2_2") (pintype "passive"))
      (node (ref "S7") (pin "1") (pinfunction "1_1") (pintype "passive"))
    )
    (net (code "97") (name "Net-(C42-Pad2)") (class "Default")
      (node (ref "C42") (pin "2") (pinfunction "2_2") (pintype "passive"))
      (node (ref "R25") (pin "2") (pinfunction "2_2") (pintype "passive"))
      (node (ref "R34") (pin "2") (pinfunction "2_2") (pintype "passive"))
      (node (ref "S8") (pin "1") (pinfunction "1_1") (pintype "passive"))
    )
    (net (code "98") (name "Net-(C47-Pad2)") (class "Default")
      (node (ref "C47") (pin "2") (pinfunction "2_2") (pintype "passive"))
      (node (ref "R24") (pin "2") (pinfunction "2_2") (pintype "passive"))
      (node (ref "R39") (pin "2") (pinfunction "2_2") (pintype "passive"))
      (node (ref "S9") (pin "1") (pinfunction "1_1") (pintype "passive"))
    )
    (net (code "99") (name "Net-(CN1-Pad1)") (class "Default")
      (node (ref "CN1") (pin "1") (pinfunction "1_1") (pintype "passive"))
      (node (ref "S4") (pin "2") (pintype "passive"))
      (node (ref "S6") (pin "2") (pintype "passive"))
    )
    (net (code "100") (name "Net-(D4-PadK)") (class "Default")
      (node (ref "D4") (pin "K") (pinfunction "K_K") (pintype "passive"))
      (node (ref "F1") (pin "2") (pinfunction "2_2") (pintype "passive"))
    )
    (net (code "101") (name "Net-(D5-K)") (class "Default")
      (node (ref "D5") (pin "2") (pinfunction "K_2") (pintype "passive"))
      (node (ref "L1") (pin "1") (pinfunction "1_1") (pintype "passive"))
      (node (ref "U3") (pin "5") (pinfunction "SW_5") (pintype "passive"))
      (node (ref "U3") (pin "6") (pinfunction "SW_6") (pintype "passive"))
    )
    (net (code "102") (name "Net-(E1-A)") (class "Default")
      (node (ref "E1") (pin "1") (pinfunction "A_1") (pintype "passive"))
      (node (ref "R10") (pin "2") (pinfunction "2_2") (pintype "passive"))
    )
    (net (code "103") (name "Net-(E2-A)") (class "Default")
      (node (ref "E2") (pin "1") (pinfunction "A_1") (pintype "passive"))
      (node (ref "R42") (pin "2") (pinfunction "2_2") (pintype "passive"))
    )
    (net (code "104") (name "Net-(E3-A)") (class "Default")
      (node (ref "E3") (pin "1") (pinfunction "A_1") (pintype "passive"))
      (node (ref "R44") (pin "2") (pinfunction "2_2") (pintype "passive"))
    )
    (net (code "105") (name "Net-(JP2-Pad7)") (class "Default")
      (node (ref "JP2") (pin "7") (pinfunction "7_7") (pintype "passive"))
      (node (ref "R1") (pin "2") (pinfunction "2_2") (pintype "passive"))
    )
    (net (code "106") (name "Net-(JP2-Pad9)") (class "Default")
      (node (ref "JP2") (pin "9") (pinfunction "9_9") (pintype "passive"))
      (node (ref "R3") (pin "2") (pinfunction "2_2") (pintype "passive"))
      (node (ref "R4") (pin "2") (pinfunction "2_2") (pintype "passive"))
    )
    (net (code "107") (name "Net-(LED1-Pad1)") (class "Default")
      (node (ref "LED1") (pin "1") (pinfunction "1_1") (pintype "passive"))
      (node (ref "R18") (pin "1") (pinfunction "1_1") (pintype "passive"))
    )
    (net (code "108") (name "Net-(P1-Pad3)") (class "Default")
      (node (ref "P1") (pin "3") (pinfunction "3_3") (pintype "passive"))
      (node (ref "R2") (pin "2") (pinfunction "2_2") (pintype "passive"))
    )
    (net (code "109") (name "Net-(P2-Pad3)") (class "Default")
      (node (ref "P2") (pin "3") (pinfunction "3_3") (pintype "passive"))
      (node (ref "R5") (pin "2") (pinfunction "2_2") (pintype "passive"))
    )
    (net (code "110") (name "Net-(Q1-B)") (class "Default")
      (node (ref "Q1") (pin "2") (pinfunction "B_2") (pintype "passive"))
      (node (ref "R6") (pin "2") (pinfunction "2_2") (pintype "passive"))
    )
    (net (code "111") (name "Net-(Q1-C)") (class "Default")
      (node (ref "LS1") (pin "2") (pinfunction "2_2") (pintype "passive"))
      (node (ref "Q1") (pin "1") (pinfunction "C_1") (pintype "passive"))
    )
    (net (code "112") (name "Net-(SW1-A1)") (class "Default")
      (node (ref "R11") (pin "2") (pinfunction "2_2") (pintype "passive"))
      (node (ref "SW1") (pin "1") (pinfunction "A1_1") (pintype "passive"))
    )
    (net (code "113") (name "Net-(SW1-A2)") (class "Default")
      (node (ref "R12") (pin "2") (pinfunction "2_2") (pintype "passive"))
      (node (ref "SW1") (pin "2") (pinfunction "A2_2") (pintype "passive"))
    )
    (net (code "114") (name "Net-(SW1-A3)") (class "Default")
      (node (ref "R13") (pin "2") (pinfunction "2_2") (pintype "passive"))
      (node (ref "SW1") (pin "3") (pinfunction "A3_3") (pintype "passive"))
    )
    (net (code "115") (name "Net-(SW1-A4)") (class "Default")
      (node (ref "R15") (pin "2") (pinfunction "2_2") (pintype "passive"))
      (node (ref "SW1") (pin "4") (pinfunction "A4_4") (pintype "passive"))
    )
    (net (code "116") (name "Net-(U1-EN)") (class "Default")
      (node (ref "C6") (pin "2") (pinfunction "2_2") (pintype "passive"))
      (node (ref "C7") (pin "2") (pinfunction "2_2") (pintype "passive"))
      (node (ref "F1") (pin "1") (pinfunction "1_1") (pintype "passive"))
      (node (ref "U1") (pin "1") (pinfunction "VIN_1") (pintype "passive"))
      (node (ref "U1") (pin "3") (pinfunction "EN_3") (pintype "passive"))
    )
    (net (code "117") (name "Net-(U3-EN)") (class "Default")
      (node (ref "R16") (pin "1") (pinfunction "1_1") (pintype "passive"))
      (node (ref "U3") (pin "2") (pinfunction "EN_2") (pintype "passive"))
    )
    (net (code "118") (name "Net-(U3-FB)") (class "Default")
      (node (ref "R14") (pin "1") (pinfunction "1_1") (pintype "passive"))
      (node (ref "R17") (pin "2") (pinfunction "2_2") (pintype "passive"))
      (node (ref "U3") (pin "1") (pinfunction "FB_1") (pintype "passive"))
    )
    (net (code "119") (name "Net-(U3-OCSET)") (class "Default")
      (node (ref "R19") (pin "1") (pinfunction "1_1") (pintype "passive"))
      (node (ref "U3") (pin "3") (pinfunction "OCSET_3") (pintype "passive"))
    )
    (net (code "120") (name "Net-(U6-VIA)") (class "Default")
      (node (ref "R31") (pin "2") (pinfunction "2_2") (pintype "passive"))
      (node (ref "U6") (pin "2") (pinfunction "VIA_2") (pintype "passive"))
    )
    (net (code "121") (name "Net-(U6-VIB)") (class "Default")
      (node (ref "R32") (pin "2") (pinfunction "2_2") (pintype "passive"))
      (node (ref "U6") (pin "3") (pinfunction "VIB_3") (pintype "passive"))
    )
    (net (code "122") (name "Net-(U8-EN)") (class "Default")
      (node (ref "R36") (pin "1") (pinfunction "1_1") (pintype "passive"))
      (node (ref "U8") (pin "1") (pinfunction "PS/SYNC_1") (pintype "passive"))
      (node (ref "U8") (pin "14") (pinfunction "EN_14") (pintype "passive"))
    )
    (net (code "123") (name "Net-(U8-FB)") (class "Default")
      (node (ref "R41") (pin "1") (pinfunction "1_1") (pintype "passive"))
      (node (ref "R43") (pin "2") (pinfunction "2_2") (pintype "passive"))
      (node (ref "U8") (pin "5") (pinfunction "FB_5") (pintype "passive"))
    )
    (net (code "124") (name "Net-(U8-L1)") (class "Default")
      (node (ref "L2") (pin "1") (pinfunction "1_1") (pintype "passive"))
      (node (ref "U8") (pin "11") (pinfunction "L1_11") (pintype "passive"))
    )
    (net (code "125") (name "Net-(U8-L2)") (class "Default")
      (node (ref "L2") (pin "2") (pinfunction "2_2") (pintype "passive"))
      (node (ref "U8") (pin "9") (pinfunction "L2_9") (pintype "passive"))
    )
    (net (code "126") (name "Net-(U8-PG)") (class "Default")
      (node (ref "R37") (pin "2") (pinfunction "2_2") (pintype "passive"))
      (node (ref "U8") (pin "2") (pinfunction "PG_2") (pintype "passive"))
    )
    (net (code "127") (name "Net-(U8-Vaux)") (class "Default")
      (node (ref "C43") (pin "2") (pinfunction "2_2") (pintype "passive"))
      (node (ref "U8") (pin "3") (pinfunction "Vaux_3") (pintype "passive"))
    )
    (net (code "128") (name "Net-(UU1-VIA)") (class "Default")
      (node (ref "R22") (pin "2") (pinfunction "2_2") (pintype "passive"))
      (node (ref "UU1") (pin "2") (pinfunction "VIA_2") (pintype "passive"))
    )
    (net (code "129") (name "Net-(UU1-VIB)") (class "Default")
      (node (ref "R23") (pin "2") (pinfunction "2_2") (pintype "passive"))
      (node (ref "UU1") (pin "3") (pinfunction "VIB_3") (pintype "passive"))
    )
    (net (code "130") (name "OPA3.3V") (class "Default")
      (node (ref "C30") (pin "2") (pinfunction "2_2") (pintype "passive"))
      (node (ref "C33") (pin "1") (pinfunction "1_1") (pintype "passive"))
      (node (ref "JP3") (pin "8") (pinfunction "8_8") (pintype "passive"))
      (node (ref "U5") (pin "5") (pinfunction "VOUT_5") (pintype "passive"))
    )
    (net (code "131") (name "VCC") (class "Default")
      (node (ref "C21") (pin "1") (pinfunction "1_1") (pintype "passive"))
      (node (ref "C22") (pin "1") (pinfunction "1_1") (pintype "passive"))
      (node (ref "C44") (pin "2") (pinfunction "2_2") (pintype "passive"))
      (node (ref "C45") (pin "2") (pinfunction "2_2") (pintype "passive"))
      (node (ref "C46") (pin "2") (pinfunction "2_2") (pintype "passive"))
      (node (ref "R16") (pin "2") (pinfunction "2_2") (pintype "passive"))
      (node (ref "R19") (pin "2") (pinfunction "2_2") (pintype "passive"))
      (node (ref "R36") (pin "2") (pinfunction "2_2") (pintype "passive"))
      (node (ref "R38") (pin "1") (pinfunction "1_1") (pintype "passive"))
      (node (ref "S4") (pin "1") (pintype "passive"))
      (node (ref "Test1") (pin "2") (pinfunction "2_2") (pintype "passive"))
      (node (ref "U3") (pin "4") (pinfunction "IN_4") (pintype "passive"))
      (node (ref "U8") (pin "12") (pinfunction "Vin_12") (pintype "passive"))
      (node (ref "U8") (pin "13") (pinfunction "Vin_13") (pintype "passive"))
    )
    (net (code "132") (name "unconnected-(*1-PA8-Pad100)") (class "Default")
      (node (ref "*1") (pin "100") (pinfunction "PA8_100") (pintype "passive"))
    )
    (net (code "133") (name "unconnected-(*1-PB3-Pad133)") (class "Default")
      (node (ref "*1") (pin "133") (pinfunction "PB3_133") (pintype "passive"))
    )
    (net (code "134") (name "unconnected-(*1-PB5-Pad135)") (class "Default")
      (node (ref "*1") (pin "135") (pinfunction "PB5_135") (pintype "passive"))
    )
    (net (code "135") (name "unconnected-(*1-PB8-Pad139)") (class "Default")
      (node (ref "*1") (pin "139") (pinfunction "PB8_139") (pintype "passive"))
    )
    (net (code "136") (name "unconnected-(*1-PB9-Pad140)") (class "Default")
      (node (ref "*1") (pin "140") (pinfunction "PB9_140") (pintype "passive"))
    )
    (net (code "137") (name "unconnected-(*1-PC2-Pad28)") (class "Default")
      (node (ref "*1") (pin "28") (pinfunction "PC2_28") (pintype "passive"))
    )
    (net (code "138") (name "unconnected-(*1-PC3-Pad29)") (class "Default")
      (node (ref "*1") (pin "29") (pinfunction "PC3_29") (pintype "passive"))
    )
    (net (code "139") (name "unconnected-(*1-PC6-Pad96)") (class "Default")
      (node (ref "*1") (pin "96") (pinfunction "PC6_96") (pintype "passive"))
    )
    (net (code "140") (name "unconnected-(*1-PC7-Pad97)") (class "Default")
      (node (ref "*1") (pin "97") (pinfunction "PC7_97") (pintype "passive"))
    )
    (net (code "141") (name "unconnected-(*1-PC8-Pad98)") (class "Default")
      (node (ref "*1") (pin "98") (pinfunction "PC8_98") (pintype "passive"))
    )
    (net (code "142") (name "unconnected-(*1-PC9-Pad99)") (class "Default")
      (node (ref "*1") (pin "99") (pinfunction "PC9_99") (pintype "passive"))
    )
    (net (code "143") (name "unconnected-(*1-PC13-Pad7)") (class "Default")
      (node (ref "*1") (pin "7") (pinfunction "PC13_7") (pintype "passive"))
    )
    (net (code "144") (name "unconnected-(*1-PD10-Pad79)") (class "Default")
      (node (ref "*1") (pin "79") (pinfunction "PD10_79") (pintype "passive"))
    )
    (net (code "145") (name "unconnected-(*1-PD11-Pad80)") (class "Default")
      (node (ref "*1") (pin "80") (pinfunction "PD11_80") (pintype "passive"))
    )
    (net (code "146") (name "unconnected-(*1-PD12-Pad81)") (class "Default")
      (node (ref "*1") (pin "81") (pinfunction "PD12_81") (pintype "passive"))
    )
    (net (code "147") (name "unconnected-(*1-PD13-Pad82)") (class "Default")
      (node (ref "*1") (pin "82") (pinfunction "PD13_82") (pintype "passive"))
    )
    (net (code "148") (name "unconnected-(*1-PD14-Pad85)") (class "Default")
      (node (ref "*1") (pin "85") (pinfunction "PD14_85") (pintype "passive"))
    )
    (net (code "149") (name "unconnected-(*1-PD15-Pad86)") (class "Default")
      (node (ref "*1") (pin "86") (pinfunction "PD15_86") (pintype "passive"))
    )
    (net (code "150") (name "unconnected-(*1-PE0-Pad141)") (class "Default")
      (node (ref "*1") (pin "141") (pinfunction "PE0_141") (pintype "passive"))
    )
    (net (code "151") (name "unconnected-(*1-PE1-Pad142)") (class "Default")
      (node (ref "*1") (pin "142") (pinfunction "PE1_142") (pintype "passive"))
    )
    (net (code "152") (name "unconnected-(*1-PE4-Pad3)") (class "Default")
      (node (ref "*1") (pin "3") (pinfunction "PE4_3") (pintype "passive"))
    )
    (net (code "153") (name "unconnected-(*1-PE6-Pad5)") (class "Default")
      (node (ref "*1") (pin "5") (pinfunction "PE6_5") (pintype "passive"))
    )
    (net (code "154") (name "unconnected-(*1-PE9-Pad60)") (class "Default")
      (node (ref "*1") (pin "60") (pinfunction "PE9_60") (pintype "passive"))
    )
    (net (code "155") (name "unconnected-(*1-PE10-Pad63)") (class "Default")
      (node (ref "*1") (pin "63") (pinfunction "PE10_63") (pintype "passive"))
    )
    (net (code "156") (name "unconnected-(*1-PE12-Pad65)") (class "Default")
      (node (ref "*1") (pin "65") (pinfunction "PE12_65") (pintype "passive"))
    )
    (net (code "157") (name "unconnected-(*1-PE14-Pad67)") (class "Default")
      (node (ref "*1") (pin "67") (pinfunction "PE14_67") (pintype "passive"))
    )
    (net (code "158") (name "unconnected-(*1-PF0-Pad10)") (class "Default")
      (node (ref "*1") (pin "10") (pinfunction "PF0_10") (pintype "passive"))
    )
    (net (code "159") (name "unconnected-(*1-PF1-Pad11)") (class "Default")
      (node (ref "*1") (pin "11") (pinfunction "PF1_11") (pintype "passive"))
    )
    (net (code "160") (name "unconnected-(*1-PF2-Pad12)") (class "Default")
      (node (ref "*1") (pin "12") (pinfunction "PF2_12") (pintype "passive"))
    )
    (net (code "161") (name "unconnected-(*1-PF3-Pad13)") (class "Default")
      (node (ref "*1") (pin "13") (pinfunction "PF3_13") (pintype "passive"))
    )
    (net (code "162") (name "unconnected-(*1-PF4-Pad14)") (class "Default")
      (node (ref "*1") (pin "14") (pinfunction "PF4_14") (pintype "passive"))
    )
    (net (code "163") (name "unconnected-(*1-PF5-Pad15)") (class "Default")
      (node (ref "*1") (pin "15") (pinfunction "PF5_15") (pintype "passive"))
    )
    (net (code "164") (name "unconnected-(*1-PF12-Pad50)") (class "Default")
      (node (ref "*1") (pin "50") (pinfunction "PF12_50") (pintype "passive"))
    )
    (net (code "165") (name "unconnected-(*1-PG8-Pad93)") (class "Default")
      (node (ref "*1") (pin "93") (pinfunction "PG8_93") (pintype "passive"))
    )
    (net (code "166") (name "unconnected-(*1-PG10-Pad125)") (class "Default")
      (node (ref "*1") (pin "125") (pinfunction "PG10_125") (pintype "passive"))
    )
    (net (code "167") (name "unconnected-(*1-PG11-Pad126)") (class "Default")
      (node (ref "*1") (pin "126") (pinfunction "PG11_126") (pintype "passive"))
    )
    (net (code "168") (name "unconnected-(*1-PG12-Pad127)") (class "Default")
      (node (ref "*1") (pin "127") (pinfunction "PG12_127") (pintype "passive"))
    )
    (net (code "169") (name "unconnected-(*1-PG15-Pad132)") (class "Default")
      (node (ref "*1") (pin "132") (pinfunction "PG15_132") (pintype "passive"))
    )
    (net (code "170") (name "unconnected-(*1-VDD-Pad95)") (class "Default")
      (node (ref "*1") (pin "95") (pinfunction "VDD_95") (pintype "passive"))
    )
    (net (code "171") (name "unconnected-(*1-VSS-Pad94)") (class "Default")
      (node (ref "*1") (pin "94") (pinfunction "VSS_94") (pintype "passive"))
    )
    (net (code "172") (name "unconnected-(*1-VSSA-Pad30)") (class "Default")
      (node (ref "*1") (pin "30") (pinfunction "VSSA_30") (pintype "passive"))
    )
    (net (code "173") (name "unconnected-(CN1-Pad3)") (class "Default")
      (node (ref "CN1") (pin "3") (pinfunction "3_3") (pintype "passive+no_connect"))
    )
    (net (code "174") (name "unconnected-(CN1-Pad4)") (class "Default")
      (node (ref "CN1") (pin "4") (pinfunction "4_4") (pintype "passive+no_connect"))
    )
    (net (code "175") (name "unconnected-(JP1-Pad7)") (class "Default")
      (node (ref "JP1") (pin "7") (pinfunction "7_7") (pintype "passive+no_connect"))
    )
    (net (code "176") (name "unconnected-(JP2-Pad6)") (class "Default")
      (node (ref "JP2") (pin "6") (pinfunction "6_6") (pintype "passive+no_connect"))
    )
    (net (code "177") (name "unconnected-(JP2-Pad8)") (class "Default")
      (node (ref "JP2") (pin "8") (pinfunction "8_8") (pintype "passive+no_connect"))
    )
    (net (code "178") (name "unconnected-(P1-Pad6)") (class "Default")
      (node (ref "P1") (pin "6") (pinfunction "6_6") (pintype "passive+no_connect"))
    )
    (net (code "179") (name "unconnected-(S4-Pad3)") (class "Default")
      (node (ref "S4") (pin "3") (pintype "passive+no_connect"))
    )
    (net (code "180") (name "unconnected-(S6-Pad3)") (class "Default")
      (node (ref "S6") (pin "3") (pintype "passive+no_connect"))
    )
    (net (code "181") (name "unconnected-(U1-NC-Pad4)") (class "Default")
      (node (ref "U1") (pin "4") (pinfunction "NC_4") (pintype "passive+no_connect"))
    )
    (net (code "182") (name "unconnected-(U2-FSY-Pad8)") (class "Default")
      (node (ref "U2") (pin "8") (pinfunction "FSY_8") (pintype "passive+no_connect"))
    )
    (net (code "183") (name "unconnected-(U2-INT-Pad7)") (class "Default")
      (node (ref "U2") (pin "7") (pinfunction "INT_7") (pintype "passive+no_connect"))
    )
    (net (code "184") (name "unconnected-(U4-NC-Pad4)") (class "Default")
      (node (ref "U4") (pin "4") (pinfunction "NC_4") (pintype "passive+no_connect"))
    )
    (net (code "185") (name "unconnected-(U5-NC-Pad4)") (class "Default")
      (node (ref "U5") (pin "4") (pinfunction "NC_4") (pintype "passive+no_connect"))
    )
    (net (code "186") (name "unconnected-(U7-NC-Pad4)") (class "Default")
      (node (ref "U7") (pin "4") (pinfunction "NC_4") (pintype "passive+no_connect"))
    )
    (net (code "187") (name "unconnected-(U8-Vsel-Pad15)") (class "Default")
      (node (ref "U8") (pin "15") (pinfunction "Vsel_15") (pintype "passive"))
    )
    (net (code "188") (name "unconnected-(WIFI1-Pad2)") (class "Default")
      (node (ref "WIFI1") (pin "2") (pinfunction "2_2") (pintype "power_in+no_connect"))
    )
    (net (code "189") (name "unconnected-(WIFI1-Pad8)") (class "Default")
      (node (ref "WIFI1") (pin "8") (pinfunction "8_8") (pintype "power_in+no_connect"))
    )
    (net (code "190") (name "unconnected-(WIFI2-Pad2)") (class "Default")
      (node (ref "WIFI2") (pin "2") (pinfunction "2_2") (pintype "power_in+no_connect"))
    )
    (net (code "191") (name "unconnected-(WIFI2-Pad8)") (class "Default")
      (node (ref "WIFI2") (pin "8") (pinfunction "8_8") (pintype "power_in+no_connect"))
    )
    (net (code "192") (name "unconnected-(X2-GND-Pad2)") (class "Default")
      (node (ref "X2") (pin "2") (pinfunction "GND_2") (pintype "passive+no_connect"))
    )
    (net (code "193") (name "unconnected-(X2-GND-Pad4)") (class "Default")
      (node (ref "X2") (pin "4") (pinfunction "GND_4") (pintype "passive+no_connect"))
    )
    (net (code "194") (name "unconnected-(mini*1-Pad3)") (class "Default")
      (node (ref "mini*1") (pin "3") (pinfunction "3_3") (pintype "passive+no_connect"))
    )
    (net (code "195") (name "unconnected-(mini*1-Pad6)") (class "Default")
      (node (ref "mini*1") (pin "6") (pinfunction "6_6") (pintype "passive+no_connect"))
    )
    (net (code "196") (name "unconnected-(mini1-Pad3)") (class "Default")
      (node (ref "mini1") (pin "3") (pinfunction "3_3") (pintype "passive+no_connect"))
    )
    (net (code "197") (name "unconnected-(mini1-Pad6)") (class "Default")
      (node (ref "mini1") (pin "6") (pinfunction "6_6") (pintype "passive+no_connect"))
    )
  )
)
